# lia_dfu_fix.net
KiCad netlist of a schematic drawn in EAGLE
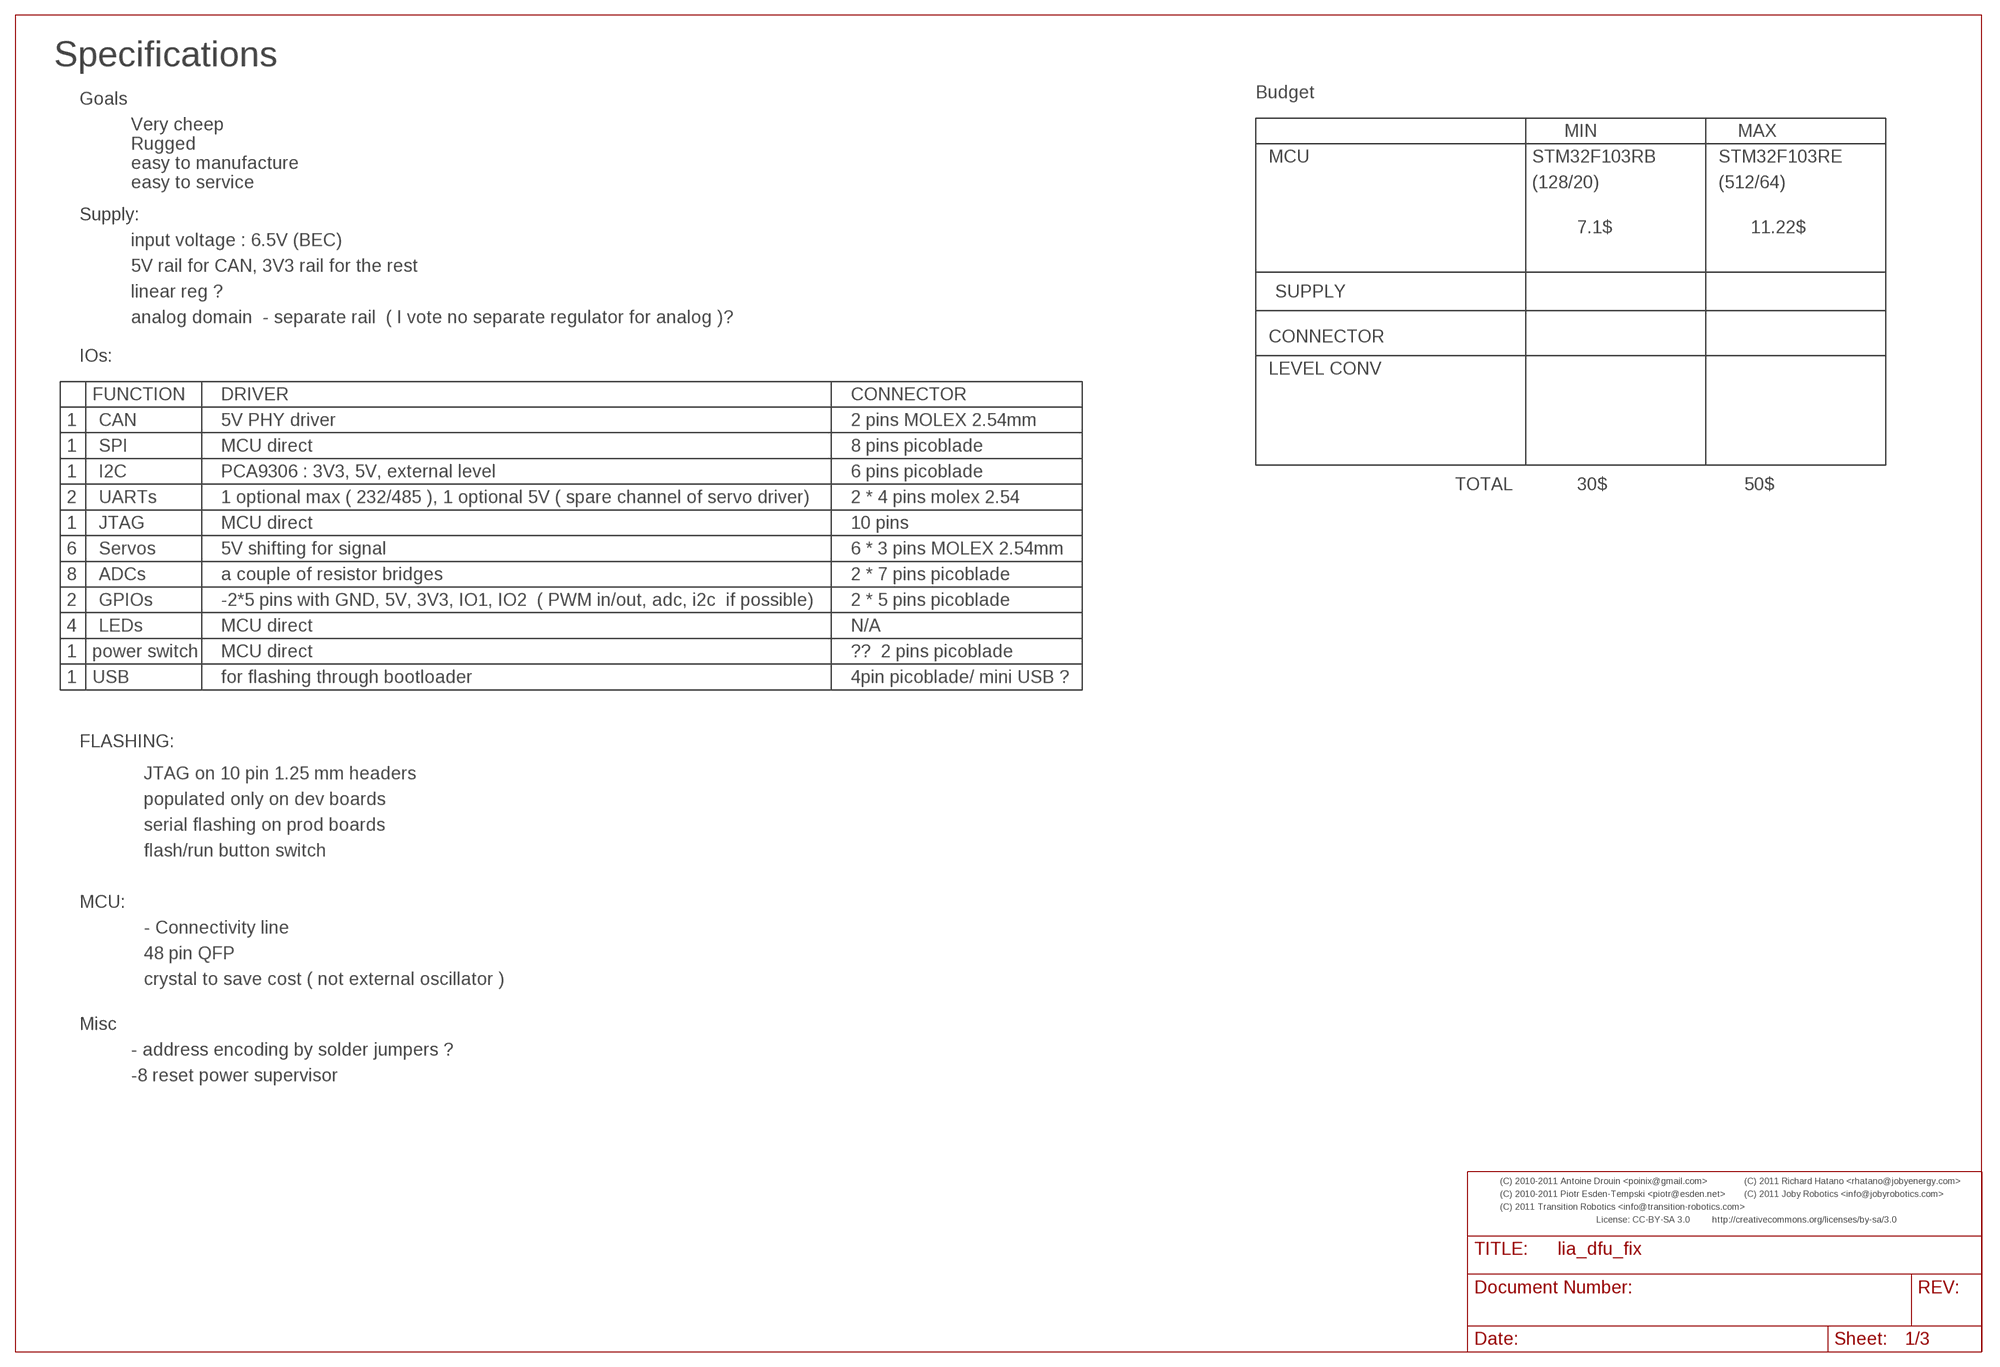
[diagram p0: schematic, sheet 1]
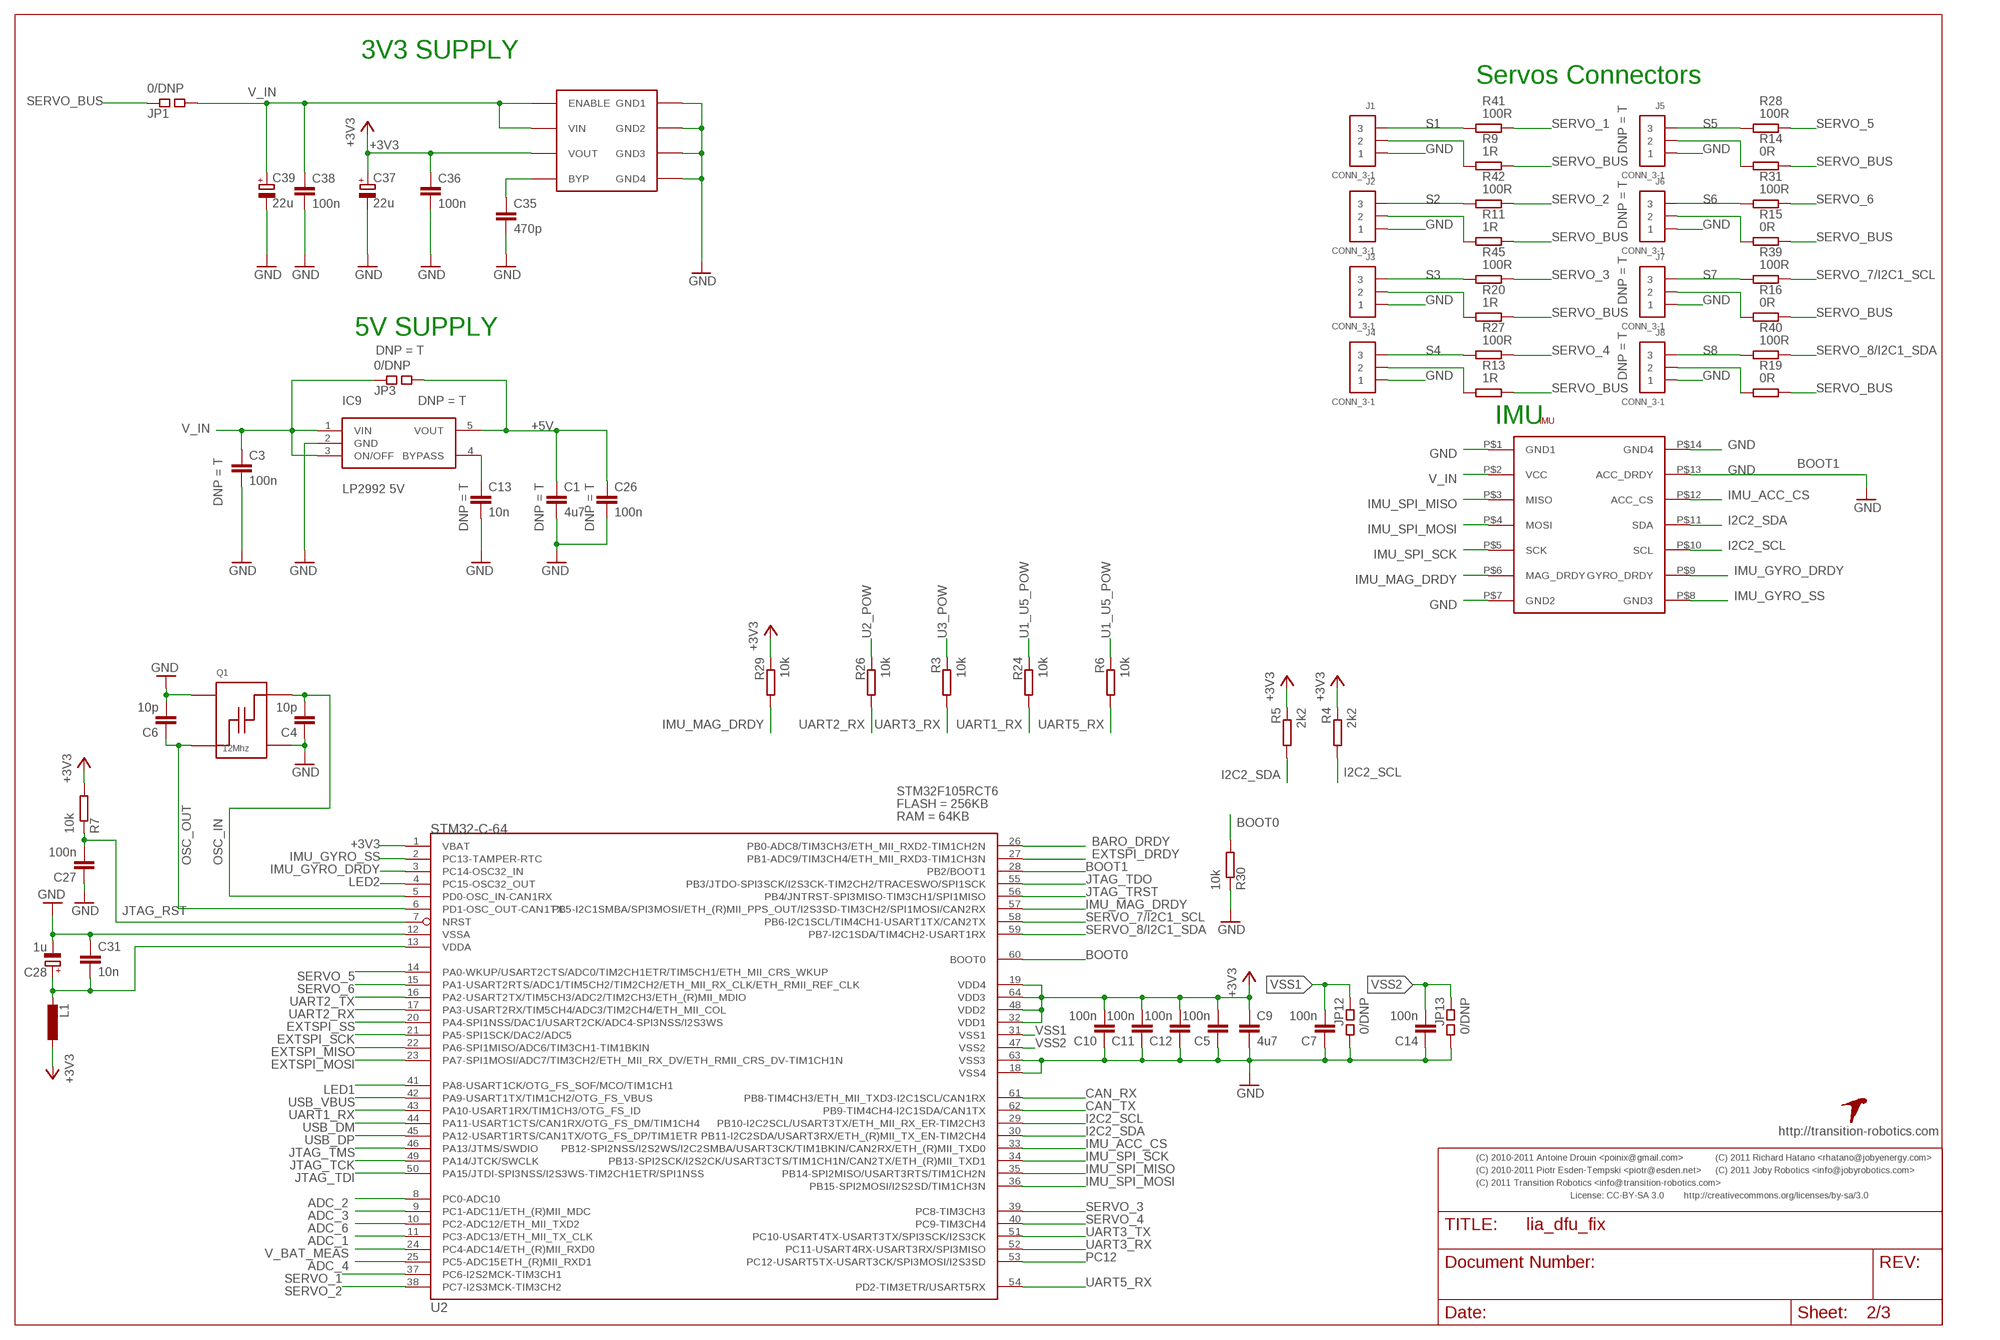
[diagram p1: schematic, sheet 2]
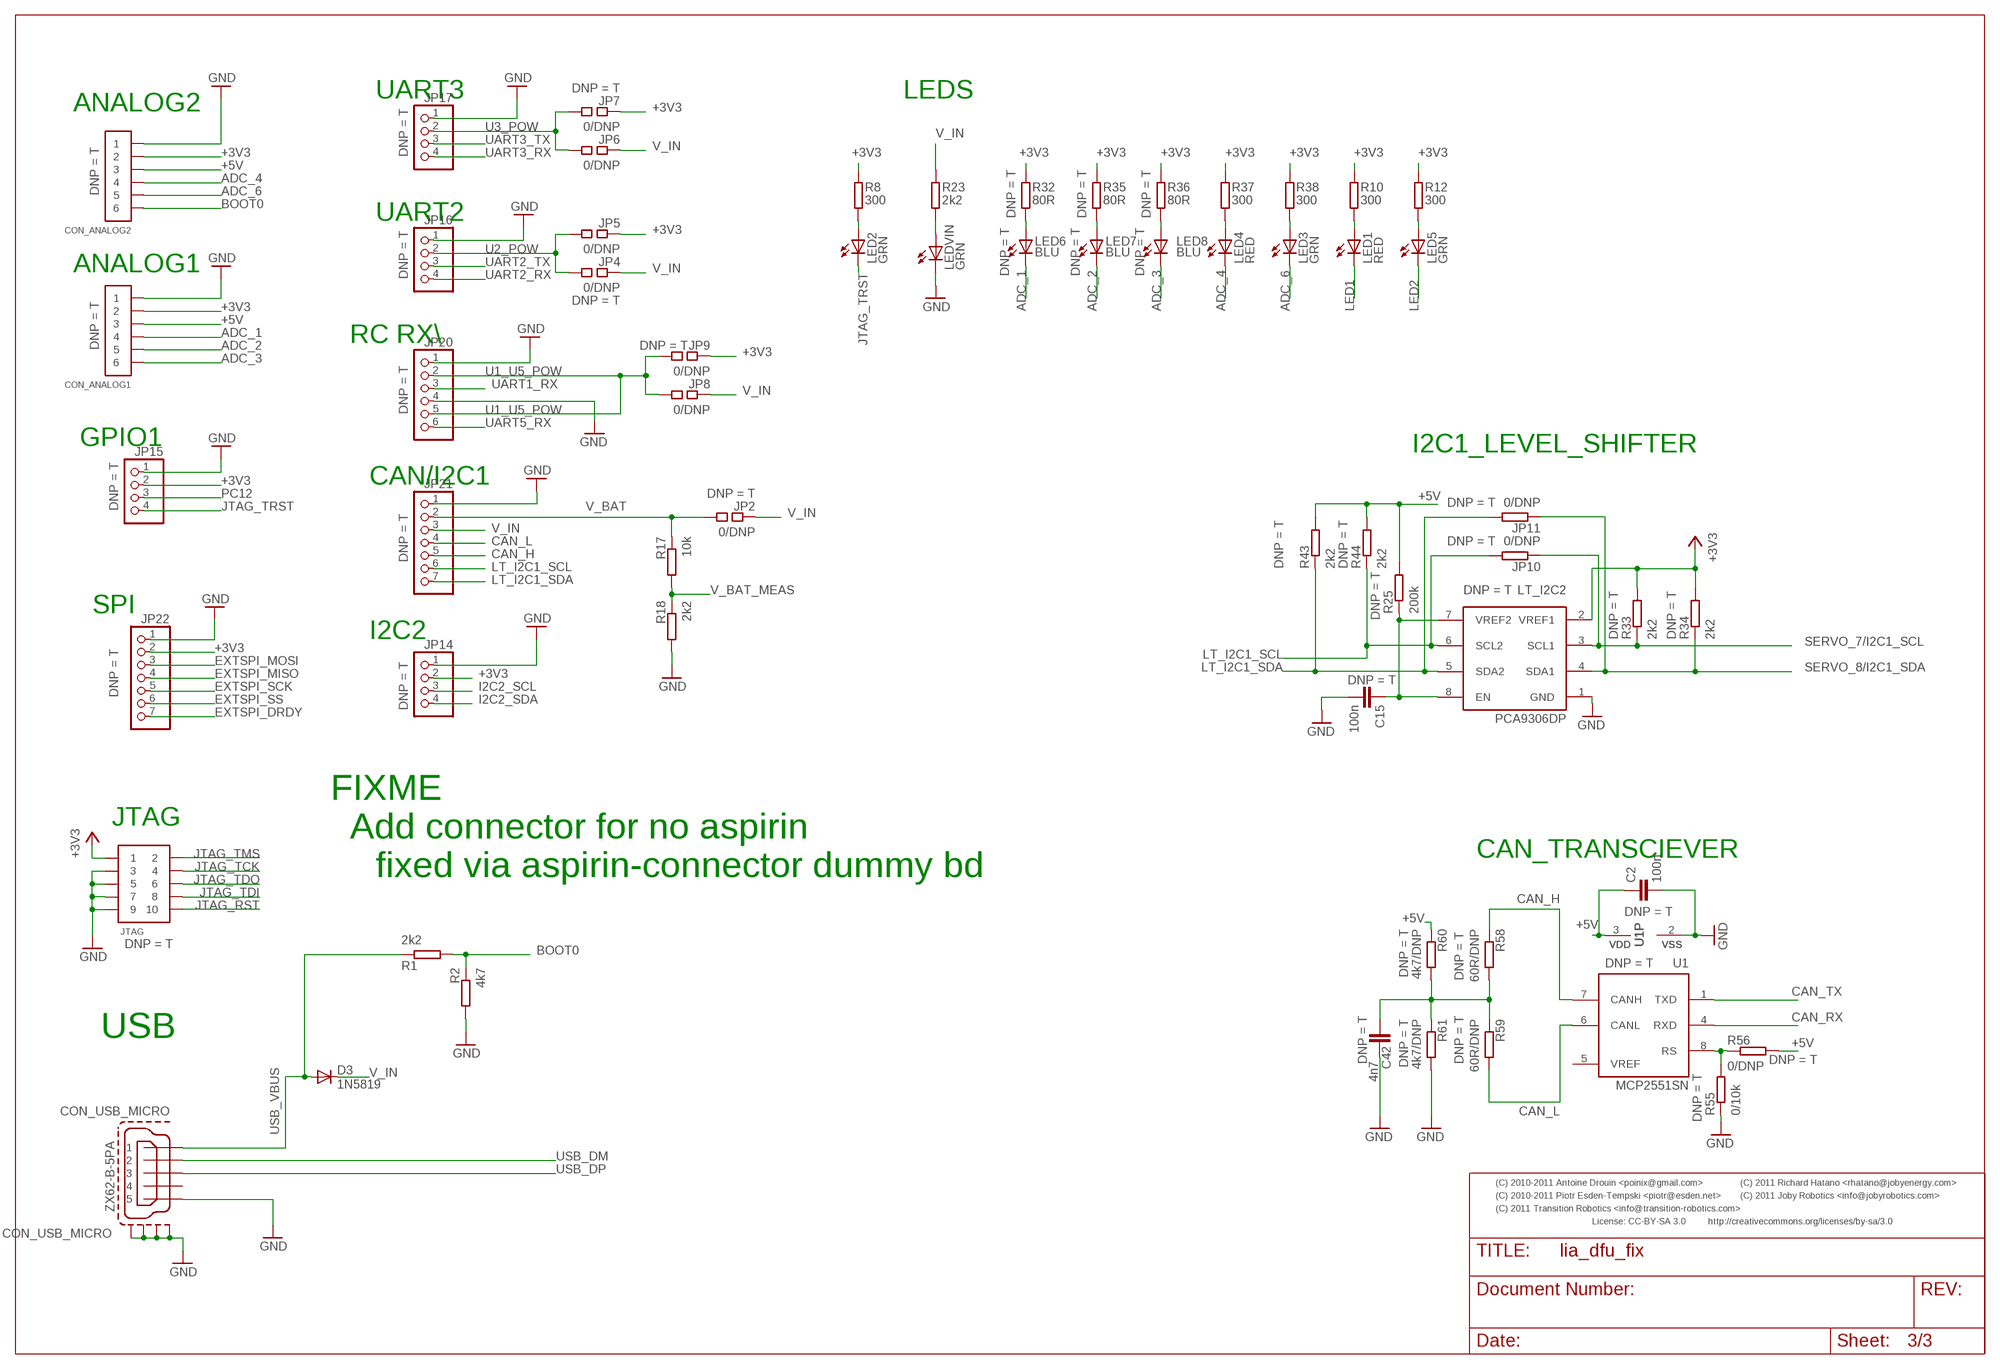
[diagram p2: schematic, sheet 3]

(export (version "E")
  (design (tool "Eeschema 10.0.6"))
  (components
    (comp (ref "C2")
      (value "100n")
      (footprint "eagle-import:0402-CAP")
      (fields (field (name "DNP") "T") (field (name "PARTNO") "cap-cer-0402-100n"))
      (libsource (lib "eagle-import") (part "CAPACITOR-0402"))
    )
    (comp (ref "C15")
      (value "100n")
      (footprint "eagle-import:0402-CAP")
      (fields (field (name "DNP") "T") (field (name "PARTNO") "cap-cer-0402-100n"))
      (libsource (lib "eagle-import") (part "CAPACITOR-0402"))
    )
    (comp (ref "C42")
      (value "4n7")
      (footprint "eagle-import:0603-CAP")
      (fields (field (name "DNP") "T") (field (name "PARTNO") "cap-cer-0603-4n7"))
      (libsource (lib "eagle-import") (part "CAPACITOR-0603"))
    )
    (comp (ref "CON_ANALOG1")
      (value "CONN_6-1-53398")
      (footprint "eagle-import:PB-53398-06")
      (fields (field (name "DNP") "T") (field (name "PARTNO") "conn-picoblade-smd-0.05in-6-vert"))
      (libsource (lib "eagle-import") (part "CONN_6-1-53398"))
    )
    (comp (ref "CON_ANALOG2")
      (value "CONN_6-1-53398")
      (footprint "eagle-import:PB-53398-06")
      (fields (field (name "DNP") "T") (field (name "PARTNO") "conn-picoblade-smd-0.05in-6-vert"))
      (libsource (lib "eagle-import") (part "CONN_6-1-53398"))
    )
    (comp (ref "CON_USB_MICRO")
      (value "ZX62-B-5PA")
      (footprint "eagle-import:ZX62-B-5PA")
      (fields (field (name "PARTNO") "conn-smd-usb-micro-b"))
      (libsource (lib "eagle-import") (part "ZX62-B-5PA"))
    )
    (comp (ref "D3")
      (value "1N5819")
      (footprint "eagle-import:MICROMELF-R")
      (fields (field (name "PARTNO") "diode-schottky-1608"))
      (libsource (lib "eagle-import") (part "DIODE-MICROMELF-R"))
    )
    (comp (ref "JP2")
      (value "0/DNP")
      (footprint "eagle-import:0402-SQJMP")
      (fields (field (name "DNP") "T") (field (name "PARTNO") "res-0402-0"))
      (libsource (lib "eagle-import") (part "SQ_JMP-0402"))
    )
    (comp (ref "JP4")
      (value "0/DNP")
      (footprint "eagle-import:0402-SQJMP")
      (fields (field (name "DNP") "T") (field (name "PARTNO") "res-0402-0"))
      (libsource (lib "eagle-import") (part "SQ_JMP-0402"))
    )
    (comp (ref "JP5")
      (value "0/DNP")
      (footprint "eagle-import:0402-SQJMP")
      (fields (field (name "PARTNO") "res-0402-0"))
      (libsource (lib "eagle-import") (part "SQ_JMP-0402"))
    )
    (comp (ref "JP6")
      (value "0/DNP")
      (footprint "eagle-import:0402-SQJMP")
      (fields (field (name "PARTNO") "res-0402-0"))
      (libsource (lib "eagle-import") (part "SQ_JMP-0402"))
    )
    (comp (ref "JP7")
      (value "0/DNP")
      (footprint "eagle-import:0402-SQJMP")
      (fields (field (name "DNP") "T") (field (name "PARTNO") "res-0402-0"))
      (libsource (lib "eagle-import") (part "SQ_JMP-0402"))
    )
    (comp (ref "JP8")
      (value "0/DNP")
      (footprint "eagle-import:0402-SQJMP")
      (fields (field (name "PARTNO") "res-0402-0"))
      (libsource (lib "eagle-import") (part "SQ_JMP-0402"))
    )
    (comp (ref "JP9")
      (value "0/DNP")
      (footprint "eagle-import:0402-SQJMP")
      (fields (field (name "DNP") "T") (field (name "PARTNO") "res-0402-0"))
      (libsource (lib "eagle-import") (part "SQ_JMP-0402"))
    )
    (comp (ref "JP10")
      (value "0/DNP")
      (footprint "eagle-import:0603-RES")
      (fields (field (name "DNP") "T") (field (name "PARTNO") "res-0603-0"))
      (libsource (lib "eagle-import") (part "RESISTOR-0603"))
    )
    (comp (ref "JP11")
      (value "0/DNP")
      (footprint "eagle-import:0603-RES")
      (fields (field (name "DNP") "T") (field (name "PARTNO") "res-0603-0"))
      (libsource (lib "eagle-import") (part "RESISTOR-0603"))
    )
    (comp (ref "JP14")
      (value "PINHD-1X4")
      (footprint "eagle-import:1X04")
      (fields (field (name "DNP") "T") (field (name "PARTNO") "conn-th-0.1in-4-1"))
      (libsource (lib "eagle-import") (part "PINHD-1X4"))
    )
    (comp (ref "JP15")
      (value "PINHD-1X4")
      (footprint "eagle-import:1X04")
      (fields (field (name "DNP") "T") (field (name "PARTNO") "conn-th-0.1in-4-1"))
      (libsource (lib "eagle-import") (part "PINHD-1X4"))
    )
    (comp (ref "JP16")
      (value "PINHD-1X4")
      (footprint "eagle-import:1X04")
      (fields (field (name "DNP") "T") (field (name "PARTNO") "conn-th-0.1in-4-1"))
      (libsource (lib "eagle-import") (part "PINHD-1X4"))
    )
    (comp (ref "JP17")
      (value "PINHD-1X4")
      (footprint "eagle-import:1X04")
      (fields (field (name "DNP") "T") (field (name "PARTNO") "conn-th-0.1in-4-1"))
      (libsource (lib "eagle-import") (part "PINHD-1X4"))
    )
    (comp (ref "JP20")
      (value "PINHD-1X6")
      (footprint "eagle-import:1X06")
      (fields (field (name "DNP") "T") (field (name "PARTNO") "conn-th-0.1in-6-1"))
      (libsource (lib "eagle-import") (part "PINHD-1X6"))
    )
    (comp (ref "JP21")
      (value "PINHD-1X7")
      (footprint "eagle-import:1X07")
      (fields (field (name "DNP") "T") (field (name "PARTNO") "conn-th-0.1in-7-1"))
      (libsource (lib "eagle-import") (part "PINHD-1X7"))
    )
    (comp (ref "JP22")
      (value "PINHD-1X7")
      (footprint "eagle-import:1X07")
      (fields (field (name "DNP") "T") (field (name "PARTNO") "conn-th-0.1in-7-1"))
      (libsource (lib "eagle-import") (part "PINHD-1X7"))
    )
    (comp (ref "JTAG")
      (value "PIN_HDR_EDG_1.27MM_5-2")
      (footprint "eagle-import:FTSH-105-DV")
      (fields (field (name "DNP") "T") (field (name "PARTNO") "conn-smd-0.05in-5-2"))
      (libsource (lib "eagle-import") (part "CONN_5-2-FTSH-V"))
    )
    (comp (ref "LED1")
      (value "RED")
      (footprint "eagle-import:0402-LED")
      (fields (field (name "PARTNO") "led-0402-red"))
      (libsource (lib "eagle-import") (part "LED-0402"))
    )
    (comp (ref "LED2")
      (value "GRN")
      (footprint "eagle-import:0402-LED")
      (fields (field (name "PARTNO") "led-0402-green"))
      (libsource (lib "eagle-import") (part "LED-0402"))
    )
    (comp (ref "LED3")
      (value "GRN")
      (footprint "eagle-import:0402-LED")
      (fields (field (name "PARTNO") "led-0402-green"))
      (libsource (lib "eagle-import") (part "LED-0402"))
    )
    (comp (ref "LED4")
      (value "RED")
      (footprint "eagle-import:0402-LED")
      (fields (field (name "PARTNO") "led-0402-red"))
      (libsource (lib "eagle-import") (part "LED-0402"))
    )
    (comp (ref "LED5")
      (value "GRN")
      (footprint "eagle-import:0402-LED")
      (fields (field (name "PARTNO") "led-0402-green"))
      (libsource (lib "eagle-import") (part "LED-0402"))
    )
    (comp (ref "LED6")
      (value "BLU")
      (footprint "eagle-import:0402-LED")
      (fields (field (name "DNP") "T") (field (name "PARTNO") "led-0402-blue"))
      (libsource (lib "eagle-import") (part "LED-0402"))
    )
    (comp (ref "LED7")
      (value "BLU")
      (footprint "eagle-import:0402-LED")
      (fields (field (name "DNP") "T") (field (name "PARTNO") "led-0402-blue"))
      (libsource (lib "eagle-import") (part "LED-0402"))
    )
    (comp (ref "LED8")
      (value "BLU")
      (footprint "eagle-import:0402-LED")
      (fields (field (name "DNP") "T") (field (name "PARTNO") "led-0402-blue"))
      (libsource (lib "eagle-import") (part "LED-0402"))
    )
    (comp (ref "LEDVIN")
      (value "GRN")
      (footprint "eagle-import:0402-LED")
      (fields (field (name "PARTNO") "led-0402-green"))
      (libsource (lib "eagle-import") (part "LED-0402"))
    )
    (comp (ref "LT_I2C2")
      (value "PCA9306DP")
      (footprint "eagle-import:TSSOP_B3")
      (fields (field (name "DNP") "T") (field (name "PARTNO") "ic-tssop8-level-trans"))
      (libsource (lib "eagle-import") (part "PCA9306DP"))
    )
    (comp (ref "R1")
      (value "2k2")
      (footprint "eagle-import:0402-RES")
      (fields (field (name "PARTNO") "res-0402-2k2"))
      (libsource (lib "eagle-import") (part "RESISTOR-0402"))
    )
    (comp (ref "R2")
      (value "4k7")
      (footprint "eagle-import:0402-RES")
      (fields (field (name "PARTNO") "res-0402-2k2"))
      (libsource (lib "eagle-import") (part "RESISTOR-0402"))
    )
    (comp (ref "R8")
      (value "300")
      (footprint "eagle-import:0402-RES")
      (fields (field (name "PARTNO") "res-0402-300"))
      (libsource (lib "eagle-import") (part "RESISTOR-0402"))
    )
    (comp (ref "R10")
      (value "300")
      (footprint "eagle-import:0402-RES")
      (fields (field (name "PARTNO") "res-0402-300"))
      (libsource (lib "eagle-import") (part "RESISTOR-0402"))
    )
    (comp (ref "R12")
      (value "300")
      (footprint "eagle-import:0402-RES")
      (fields (field (name "PARTNO") "res-0402-300"))
      (libsource (lib "eagle-import") (part "RESISTOR-0402"))
    )
    (comp (ref "R17")
      (value "10k")
      (footprint "eagle-import:0402-RES")
      (fields (field (name "PARTNO") "res-0402-10k"))
      (libsource (lib "eagle-import") (part "RESISTOR-0402"))
    )
    (comp (ref "R18")
      (value "2k2")
      (footprint "eagle-import:0402-RES")
      (fields (field (name "PARTNO") "res-0402-2k2"))
      (libsource (lib "eagle-import") (part "RESISTOR-0402"))
    )
    (comp (ref "R23")
      (value "2k2")
      (footprint "eagle-import:0402-RES")
      (fields (field (name "PARTNO") "res-0402-2k2"))
      (libsource (lib "eagle-import") (part "RESISTOR-0402"))
    )
    (comp (ref "R25")
      (value "200k")
      (footprint "eagle-import:0402-RES")
      (fields (field (name "DNP") "T") (field (name "PARTNO") "res-0402-200k"))
      (libsource (lib "eagle-import") (part "RESISTOR-0402"))
    )
    (comp (ref "R32")
      (value "80R")
      (footprint "eagle-import:0402-RES")
      (fields (field (name "DNP") "T") (field (name "PARTNO") "res-0402-80"))
      (libsource (lib "eagle-import") (part "RESISTOR-0402"))
    )
    (comp (ref "R33")
      (value "2k2")
      (footprint "eagle-import:0402-RES")
      (fields (field (name "DNP") "T") (field (name "PARTNO") "res-0402-2k2"))
      (libsource (lib "eagle-import") (part "RESISTOR-0402"))
    )
    (comp (ref "R34")
      (value "2k2")
      (footprint "eagle-import:0402-RES")
      (fields (field (name "DNP") "T") (field (name "PARTNO") "res-0402-2k2"))
      (libsource (lib "eagle-import") (part "RESISTOR-0402"))
    )
    (comp (ref "R35")
      (value "80R")
      (footprint "eagle-import:0402-RES")
      (fields (field (name "DNP") "T") (field (name "PARTNO") "res-0402-80"))
      (libsource (lib "eagle-import") (part "RESISTOR-0402"))
    )
    (comp (ref "R36")
      (value "80R")
      (footprint "eagle-import:0402-RES")
      (fields (field (name "DNP") "T") (field (name "PARTNO") "res-0402-80"))
      (libsource (lib "eagle-import") (part "RESISTOR-0402"))
    )
    (comp (ref "R37")
      (value "300")
      (footprint "eagle-import:0402-RES")
      (fields (field (name "PARTNO") "res-0402-300"))
      (libsource (lib "eagle-import") (part "RESISTOR-0402"))
    )
    (comp (ref "R38")
      (value "300")
      (footprint "eagle-import:0402-RES")
      (fields (field (name "PARTNO") "res-0402-300"))
      (libsource (lib "eagle-import") (part "RESISTOR-0402"))
    )
    (comp (ref "R43")
      (value "2k2")
      (footprint "eagle-import:0402-RES")
      (fields (field (name "DNP") "T") (field (name "PARTNO") "res-0402-1k5"))
      (libsource (lib "eagle-import") (part "RESISTOR-0402"))
    )
    (comp (ref "R44")
      (value "2k2")
      (footprint "eagle-import:0402-RES")
      (fields (field (name "DNP") "T") (field (name "PARTNO") "res-0402-1k5"))
      (libsource (lib "eagle-import") (part "RESISTOR-0402"))
    )
    (comp (ref "R55")
      (value "0/10k")
      (footprint "eagle-import:0402-RES")
      (fields (field (name "DNP") "T") (field (name "PARTNO") "res-0402-10k"))
      (libsource (lib "eagle-import") (part "RESISTOR-0402"))
    )
    (comp (ref "R56")
      (value "0/DNP")
      (footprint "eagle-import:0402-RES")
      (fields (field (name "DNP") "T") (field (name "PARTNO") "res-0402-0"))
      (libsource (lib "eagle-import") (part "RESISTOR-0402"))
    )
    (comp (ref "R58")
      (value "60R/DNP")
      (footprint "eagle-import:0402-RES")
      (fields (field (name "DNP") "T") (field (name "PARTNO") "res-0402-60.4"))
      (libsource (lib "eagle-import") (part "RESISTOR-0402"))
    )
    (comp (ref "R59")
      (value "60R/DNP")
      (footprint "eagle-import:0402-RES")
      (fields (field (name "DNP") "T") (field (name "PARTNO") "res-0402-60.4"))
      (libsource (lib "eagle-import") (part "RESISTOR-0402"))
    )
    (comp (ref "R60")
      (value "4k7/DNP")
      (footprint "eagle-import:0402-RES")
      (fields (field (name "DNP") "T") (field (name "PARTNO") "res-0402-4k7"))
      (libsource (lib "eagle-import") (part "RESISTOR-0402"))
    )
    (comp (ref "R61")
      (value "4k7/DNP")
      (footprint "eagle-import:0402-RES")
      (fields (field (name "DNP") "T") (field (name "PARTNO") "res-0402-4k7"))
      (libsource (lib "eagle-import") (part "RESISTOR-0402"))
    )
    (comp (ref "U1")
      (value "MCP2551SN")
      (footprint "eagle-import:SO-08")
      (fields (field (name "DNP") "T") (field (name "PARTNO") "ic-so8-can"))
      (libsource (lib "eagle-import") (part "MCP2551SN"))
    )
    (comp (ref "C1")
      (value "4u7")
      (footprint "eagle-import:0805-CAP")
      (fields (field (name "DNP") "T") (field (name "PARTNO") "cap-cer-0805-4u7"))
      (libsource (lib "eagle-import") (part "CAPACITOR-0805"))
    )
    (comp (ref "C3")
      (value "100n")
      (footprint "eagle-import:0603-CAP")
      (fields (field (name "DNP") "T") (field (name "PARTNO") "cap-cer-0603-100n"))
      (libsource (lib "eagle-import") (part "CAPACITOR-0603"))
    )
    (comp (ref "C4")
      (value "10p")
      (footprint "eagle-import:0402-CAP")
      (fields (field (name "PARTNO") "cap-cer-0402-10p"))
      (libsource (lib "eagle-import") (part "CAPACITOR-0402"))
    )
    (comp (ref "C5")
      (value "100n")
      (footprint "eagle-import:0402-CAP")
      (fields (field (name "PARTNO") "cap-cer-0402-100n"))
      (libsource (lib "eagle-import") (part "CAPACITOR-0402"))
    )
    (comp (ref "C6")
      (value "10p")
      (footprint "eagle-import:0402-CAP")
      (fields (field (name "PARTNO") "cap-cer-0402-10p"))
      (libsource (lib "eagle-import") (part "CAPACITOR-0402"))
    )
    (comp (ref "C7")
      (value "100n")
      (footprint "eagle-import:0402-CAP")
      (fields (field (name "PARTNO") "cap-cer-0402-100n"))
      (libsource (lib "eagle-import") (part "CAPACITOR-0402"))
    )
    (comp (ref "C9")
      (value "4u7")
      (footprint "eagle-import:0805-CAP")
      (fields (field (name "PARTNO") "cap-cer-0805-4u7"))
      (libsource (lib "eagle-import") (part "CAPACITOR-0805"))
    )
    (comp (ref "C10")
      (value "100n")
      (footprint "eagle-import:0402-CAP")
      (fields (field (name "PARTNO") "cap-cer-0402-100n"))
      (libsource (lib "eagle-import") (part "CAPACITOR-0402"))
    )
    (comp (ref "C11")
      (value "100n")
      (footprint "eagle-import:0402-CAP")
      (fields (field (name "PARTNO") "cap-cer-0402-100n"))
      (libsource (lib "eagle-import") (part "CAPACITOR-0402"))
    )
    (comp (ref "C12")
      (value "100n")
      (footprint "eagle-import:0402-CAP")
      (fields (field (name "PARTNO") "cap-cer-0402-100n"))
      (libsource (lib "eagle-import") (part "CAPACITOR-0402"))
    )
    (comp (ref "C13")
      (value "10n")
      (footprint "eagle-import:0402-CAP")
      (fields (field (name "DNP") "T") (field (name "PARTNO") "cap-cer-0402-10n"))
      (libsource (lib "eagle-import") (part "CAPACITOR-0402"))
    )
    (comp (ref "C14")
      (value "100n")
      (footprint "eagle-import:0402-CAP")
      (fields (field (name "PARTNO") "cap-cer-0402-100n"))
      (libsource (lib "eagle-import") (part "CAPACITOR-0402"))
    )
    (comp (ref "C26")
      (value "100n")
      (footprint "eagle-import:0603-CAP")
      (fields (field (name "DNP") "T") (field (name "PARTNO") "cap-cer-0603-100n"))
      (libsource (lib "eagle-import") (part "CAPACITOR-0603"))
    )
    (comp (ref "C27")
      (value "100n")
      (footprint "eagle-import:0402-CAP")
      (fields (field (name "PARTNO") "cap-cer-0402-100n"))
      (libsource (lib "eagle-import") (part "CAPACITOR-0402"))
    )
    (comp (ref "C28")
      (value "1u")
      (footprint "eagle-import:0603-POL-CAP")
      (fields (field (name "PARTNO") "cap-tan-0603-1u"))
      (libsource (lib "eagle-import") (part "CAPACITOR-POL-0603"))
    )
    (comp (ref "C31")
      (value "10n")
      (footprint "eagle-import:0402-CAP")
      (fields (field (name "PARTNO") "cap-cer-0402-10n"))
      (libsource (lib "eagle-import") (part "CAPACITOR-0402"))
    )
    (comp (ref "C35")
      (value "470p")
      (footprint "eagle-import:0402-CAP")
      (fields (field (name "PARTNO") "cap-cer-0402-470p"))
      (libsource (lib "eagle-import") (part "CAPACITOR-0402"))
    )
    (comp (ref "C36")
      (value "100n")
      (footprint "eagle-import:0603-CAP")
      (fields (field (name "PARTNO") "cap-cer-0603-100n"))
      (libsource (lib "eagle-import") (part "CAPACITOR-0603"))
    )
    (comp (ref "C37")
      (value "22u")
      (footprint "eagle-import:3528_B")
      (fields (field (name "PARTNO") "cap-tan-B-22u-16v"))
      (libsource (lib "eagle-import") (part "CAPACITOR-POLB"))
    )
    (comp (ref "C38")
      (value "100n")
      (footprint "eagle-import:0402-CAP")
      (fields (field (name "PARTNO") "cap-cer-0402-100n"))
      (libsource (lib "eagle-import") (part "CAPACITOR-0402"))
    )
    (comp (ref "C39")
      (value "22u")
      (footprint "eagle-import:3528_B")
      (fields (field (name "PARTNO") "cap-tan-B-22u-16v"))
      (libsource (lib "eagle-import") (part "CAPACITOR-POLB"))
    )
    (comp (ref "IC9")
      (value "LP2992 5V")
      (footprint "eagle-import:SOT23-5")
      (fields (field (name "DNP") "T") (field (name "PARTNO") "vreg-sot-23-5-5v"))
      (libsource (lib "eagle-import") (part "LP2992"))
    )
    (comp (ref "IMU")
      (value "ASPIRIN")
      (footprint "eagle-import:ASPIRIN_1")
      (fields (field (name "PARTNO") "pcb-ass-aspirin"))
      (libsource (lib "eagle-import") (part "ASPIRIN"))
    )
    (comp (ref "J1")
      (value "CONN_3-1")
      (footprint "eagle-import:SIP1X3_100")
      (fields (field (name "PARTNO") "conn-th-0.1in-3-2-ra"))
      (libsource (lib "eagle-import") (part "CONN_3-1"))
    )
    (comp (ref "J2")
      (value "CONN_3-1")
      (footprint "eagle-import:SIP1X3_100")
      (fields (field (name "PARTNO") "conn-th-0.1in-3-2-ra"))
      (libsource (lib "eagle-import") (part "CONN_3-1"))
    )
    (comp (ref "J3")
      (value "CONN_3-1")
      (footprint "eagle-import:SIP1X3_100")
      (fields (field (name "PARTNO") "conn-th-0.1in-3-2-ra"))
      (libsource (lib "eagle-import") (part "CONN_3-1"))
    )
    (comp (ref "J4")
      (value "CONN_3-1")
      (footprint "eagle-import:SIP1X3_100")
      (fields (field (name "PARTNO") "conn-th-0.1in-3-2-ra"))
      (libsource (lib "eagle-import") (part "CONN_3-1"))
    )
    (comp (ref "J5")
      (value "CONN_3-1")
      (footprint "eagle-import:SIP1X3_100")
      (fields (field (name "DNP") "T") (field (name "PARTNO") "conn-th-0.1in-3-2-ra"))
      (libsource (lib "eagle-import") (part "CONN_3-1"))
    )
    (comp (ref "J6")
      (value "CONN_3-1")
      (footprint "eagle-import:SIP1X3_100")
      (fields (field (name "DNP") "T") (field (name "PARTNO") "conn-th-0.1in-3-2-ra"))
      (libsource (lib "eagle-import") (part "CONN_3-1"))
    )
    (comp (ref "J7")
      (value "CONN_3-1")
      (footprint "eagle-import:SIP1X3_100")
      (fields (field (name "DNP") "T") (field (name "PARTNO") "conn-th-0.1in-3-2-ra"))
      (libsource (lib "eagle-import") (part "CONN_3-1"))
    )
    (comp (ref "J8")
      (value "CONN_3-1")
      (footprint "eagle-import:SIP1X3_100")
      (fields (field (name "DNP") "T") (field (name "PARTNO") "conn-th-0.1in-3-2-ra"))
      (libsource (lib "eagle-import") (part "CONN_3-1"))
    )
    (comp (ref "JP1")
      (value "0/DNP")
      (footprint "eagle-import:0402-SQJMP")
      (fields (field (name "PARTNO") "res-0402-0"))
      (libsource (lib "eagle-import") (part "SQ_JMP-0402"))
    )
    (comp (ref "JP3")
      (value "0/DNP")
      (footprint "eagle-import:0402-SQJMP")
      (fields (field (name "DNP") "T") (field (name "PARTNO") "res-0402-0"))
      (libsource (lib "eagle-import") (part "SQ_JMP-0402"))
    )
    (comp (ref "JP12")
      (value "0/DNP")
      (footprint "eagle-import:0402-SQJMP")
      (fields (field (name "PARTNO") "res-0402-0"))
      (libsource (lib "eagle-import") (part "SQ_JMP-0402"))
    )
    (comp (ref "JP13")
      (value "0/DNP")
      (footprint "eagle-import:0402-SQJMP")
      (fields (field (name "PARTNO") "res-0402-0"))
      (libsource (lib "eagle-import") (part "SQ_JMP-0402"))
    )
    (comp (ref "L1")
      (value "INDUCTOR-0603")
      (footprint "eagle-import:0603-IND")
      (fields (field (name "PARTNO") "ferrite-0603-600ohm"))
      (libsource (lib "eagle-import") (part "INDUCTOR-0603"))
    )
    (comp (ref "Q1")
      (value "12Mhz")
      (footprint "eagle-import:ABM8")
      (fields (field (name "PARTNO") "xtal-abm8-12mhz"))
      (libsource (lib "eagle-import") (part "ABM8"))
    )
    (comp (ref "R3")
      (value "10k")
      (footprint "eagle-import:0402-RES")
      (fields (field (name "PARTNO") "res-0402-10k"))
      (libsource (lib "eagle-import") (part "RESISTOR-0402"))
    )
    (comp (ref "R4")
      (value "2k2")
      (footprint "eagle-import:0402-RES")
      (fields (field (name "PARTNO") "res-0402-2k2"))
      (libsource (lib "eagle-import") (part "RESISTOR-0402"))
    )
    (comp (ref "R5")
      (value "2k2")
      (footprint "eagle-import:0402-RES")
      (fields (field (name "PARTNO") "res-0402-2k2"))
      (libsource (lib "eagle-import") (part "RESISTOR-0402"))
    )
    (comp (ref "R6")
      (value "10k")
      (footprint "eagle-import:0402-RES")
      (fields (field (name "PARTNO") "res-0402-10k"))
      (libsource (lib "eagle-import") (part "RESISTOR-0402"))
    )
    (comp (ref "R7")
      (value "10k")
      (footprint "eagle-import:0402-RES")
      (fields (field (name "PARTNO") "res-0402-10k"))
      (libsource (lib "eagle-import") (part "RESISTOR-0402"))
    )
    (comp (ref "R9")
      (value "1R")
      (footprint "eagle-import:1206-RES")
      (fields (field (name "PARTNO") "res-1206-1"))
      (libsource (lib "eagle-import") (part "RESISTOR-1206"))
    )
    (comp (ref "R11")
      (value "1R")
      (footprint "eagle-import:1206-RES")
      (fields (field (name "PARTNO") "res-1206-1"))
      (libsource (lib "eagle-import") (part "RESISTOR-1206"))
    )
    (comp (ref "R13")
      (value "1R")
      (footprint "eagle-import:1206-RES")
      (fields (field (name "PARTNO") "res-1206-1"))
      (libsource (lib "eagle-import") (part "RESISTOR-1206"))
    )
    (comp (ref "R14")
      (value "0R")
      (footprint "eagle-import:1206-RES")
      (fields (field (name "PARTNO") "res-1206-0"))
      (libsource (lib "eagle-import") (part "RESISTOR-1206"))
    )
    (comp (ref "R15")
      (value "0R")
      (footprint "eagle-import:1206-RES")
      (fields (field (name "PARTNO") "res-1206-0"))
      (libsource (lib "eagle-import") (part "RESISTOR-1206"))
    )
    (comp (ref "R16")
      (value "0R")
      (footprint "eagle-import:1206-RES")
      (fields (field (name "PARTNO") "res-1206-0"))
      (libsource (lib "eagle-import") (part "RESISTOR-1206"))
    )
    (comp (ref "R19")
      (value "0R")
      (footprint "eagle-import:1206-RES")
      (fields (field (name "PARTNO") "res-1206-0"))
      (libsource (lib "eagle-import") (part "RESISTOR-1206"))
    )
    (comp (ref "R20")
      (value "1R")
      (footprint "eagle-import:1206-RES")
      (fields (field (name "PARTNO") "res-1206-1"))
      (libsource (lib "eagle-import") (part "RESISTOR-1206"))
    )
    (comp (ref "R24")
      (value "10k")
      (footprint "eagle-import:0402-RES")
      (fields (field (name "PARTNO") "res-0402-10k"))
      (libsource (lib "eagle-import") (part "RESISTOR-0402"))
    )
    (comp (ref "R26")
      (value "10k")
      (footprint "eagle-import:0402-RES")
      (fields (field (name "PARTNO") "res-0402-10k"))
      (libsource (lib "eagle-import") (part "RESISTOR-0402"))
    )
    (comp (ref "R27")
      (value "100R")
      (footprint "eagle-import:0402-RES")
      (fields (field (name "PARTNO") "res-0402-100"))
      (libsource (lib "eagle-import") (part "RESISTOR-0402"))
    )
    (comp (ref "R28")
      (value "100R")
      (footprint "eagle-import:0402-RES")
      (fields (field (name "PARTNO") "res-0402-100"))
      (libsource (lib "eagle-import") (part "RESISTOR-0402"))
    )
    (comp (ref "R29")
      (value "10k")
      (footprint "eagle-import:0402-RES")
      (fields (field (name "PARTNO") "res-0402-10k"))
      (libsource (lib "eagle-import") (part "RESISTOR-0402"))
    )
    (comp (ref "R30")
      (value "10k")
      (footprint "eagle-import:0402-RES")
      (fields (field (name "PARTNO") "res-0402-10k"))
      (libsource (lib "eagle-import") (part "RESISTOR-0402"))
    )
    (comp (ref "R31")
      (value "100R")
      (footprint "eagle-import:0402-RES")
      (fields (field (name "PARTNO") "res-0402-100"))
      (libsource (lib "eagle-import") (part "RESISTOR-0402"))
    )
    (comp (ref "R39")
      (value "100R")
      (footprint "eagle-import:0402-RES")
      (fields (field (name "PARTNO") "res-0402-100"))
      (libsource (lib "eagle-import") (part "RESISTOR-0402"))
    )
    (comp (ref "R40")
      (value "100R")
      (footprint "eagle-import:0402-RES")
      (fields (field (name "PARTNO") "res-0402-100"))
      (libsource (lib "eagle-import") (part "RESISTOR-0402"))
    )
    (comp (ref "R41")
      (value "100R")
      (footprint "eagle-import:0402-RES")
      (fields (field (name "PARTNO") "res-0402-100"))
      (libsource (lib "eagle-import") (part "RESISTOR-0402"))
    )
    (comp (ref "R42")
      (value "100R")
      (footprint "eagle-import:0402-RES")
      (fields (field (name "PARTNO") "res-0402-100"))
      (libsource (lib "eagle-import") (part "RESISTOR-0402"))
    )
    (comp (ref "R45")
      (value "100R")
      (footprint "eagle-import:0402-RES")
      (fields (field (name "PARTNO") "res-0402-100"))
      (libsource (lib "eagle-import") (part "RESISTOR-0402"))
    )
    (comp (ref "U$1")
      (value "TR-LOGO")
      (footprint "eagle-import:TR-LOGO")
      (libsource (lib "eagle-import") (part "TR-LOGO"))
    )
    (comp (ref "U2")
      (value "STM32-C-64")
      (footprint "eagle-import:LQFP64")
      (fields
        (field (name "FLASH") "256KB")
        (field (name "PARTNO") "mcu-lqfp-64-stm32")
        (field (name "PART_NR") "STM32F105RCT6")
        (field (name "RAM") "64KB")
      )
      (libsource (lib "eagle-import") (part "STM32-C-64"))
    )
    (comp (ref "VREG1")
      (value "MIC5209")
      (footprint "eagle-import:SOIC8")
      (fields (field (name "PARTNO") "vreg-so8-3v3"))
      (libsource (lib "eagle-import") (part "MIC5209"))
    )
  )
  (nets
    (net (code "1") (name "+3V3") (class "Default")
      (node (ref "C10") (pin "P$2") (pinfunction "2_P$2") (pintype "passive"))
      (node (ref "C11") (pin "P$2") (pinfunction "2_P$2") (pintype "passive"))
      (node (ref "C12") (pin "P$2") (pinfunction "2_P$2") (pintype "passive"))
      (node (ref "C36") (pin "P$1") (pinfunction "1_P$1") (pintype "passive"))
      (node (ref "C37") (pin "+") (pinfunction "+_+") (pintype "passive"))
      (node (ref "C5") (pin "P$2") (pinfunction "2_P$2") (pintype "passive"))
      (node (ref "C9") (pin "P$1") (pinfunction "1_P$1") (pintype "passive"))
      (node (ref "CON_ANALOG1") (pin "2") (pinfunction "2_2") (pintype "bidirectional"))
      (node (ref "CON_ANALOG2") (pin "2") (pinfunction "2_2") (pintype "bidirectional"))
      (node (ref "JP14") (pin "2") (pinfunction "2_2") (pintype "passive"))
      (node (ref "JP15") (pin "2") (pinfunction "2_2") (pintype "passive"))
      (node (ref "JP22") (pin "2") (pinfunction "2_2") (pintype "passive"))
      (node (ref "JP5") (pin "P$1") (pinfunction "1_P$1") (pintype "passive"))
      (node (ref "JP7") (pin "P$1") (pinfunction "1_P$1") (pintype "passive"))
      (node (ref "JP9") (pin "P$1") (pinfunction "1_P$1") (pintype "passive"))
      (node (ref "JTAG") (pin "1") (pinfunction "1_1") (pintype "bidirectional"))
      (node (ref "L1") (pin "P$1") (pinfunction "1_P$1") (pintype "passive"))
      (node (ref "LT_I2C2") (pin "2") (pinfunction "VREF1_2") (pintype "bidirectional"))
      (node (ref "R10") (pin "P$2") (pinfunction "2_P$2") (pintype "passive"))
      (node (ref "R12") (pin "P$2") (pinfunction "2_P$2") (pintype "passive"))
      (node (ref "R29") (pin "P$1") (pinfunction "1_P$1") (pintype "passive"))
      (node (ref "R32") (pin "P$2") (pinfunction "2_P$2") (pintype "passive"))
      (node (ref "R33") (pin "P$2") (pinfunction "2_P$2") (pintype "passive"))
      (node (ref "R34") (pin "P$2") (pinfunction "2_P$2") (pintype "passive"))
      (node (ref "R35") (pin "P$2") (pinfunction "2_P$2") (pintype "passive"))
      (node (ref "R36") (pin "P$2") (pinfunction "2_P$2") (pintype "passive"))
      (node (ref "R37") (pin "P$2") (pinfunction "2_P$2") (pintype "passive"))
      (node (ref "R38") (pin "P$2") (pinfunction "2_P$2") (pintype "passive"))
      (node (ref "R4") (pin "P$1") (pinfunction "1_P$1") (pintype "passive"))
      (node (ref "R5") (pin "P$1") (pinfunction "1_P$1") (pintype "passive"))
      (node (ref "R7") (pin "P$2") (pinfunction "2_P$2") (pintype "passive"))
      (node (ref "R8") (pin "P$2") (pinfunction "2_P$2") (pintype "passive"))
      (node (ref "U2") (pin "1") (pinfunction "VBAT_1") (pintype "power_in"))
      (node (ref "U2") (pin "19") (pinfunction "VDD4_19") (pintype "bidirectional"))
      (node (ref "U2") (pin "32") (pinfunction "VDD1_32") (pintype "power_in"))
      (node (ref "U2") (pin "48") (pinfunction "VDD2_48") (pintype "power_in"))
      (node (ref "U2") (pin "64") (pinfunction "VDD3_64") (pintype "power_in"))
      (node (ref "VREG1") (pin "3") (pinfunction "VOUT_3") (pintype "bidirectional"))
    )
    (net (code "2") (name "+5V") (class "Default")
      (node (ref "C1") (pin "P$1") (pinfunction "1_P$1") (pintype "passive"))
      (node (ref "C2") (pin "P$1") (pinfunction "1_P$1") (pintype "passive"))
      (node (ref "C26") (pin "P$1") (pinfunction "1_P$1") (pintype "passive"))
      (node (ref "CON_ANALOG1") (pin "3") (pinfunction "3_3") (pintype "bidirectional"))
      (node (ref "CON_ANALOG2") (pin "3") (pinfunction "3_3") (pintype "bidirectional"))
      (node (ref "IC9") (pin "5") (pinfunction "VOUT_5") (pintype "bidirectional"))
      (node (ref "JP3") (pin "P$2") (pinfunction "2_P$2") (pintype "passive"))
      (node (ref "R25") (pin "P$2") (pinfunction "2_P$2") (pintype "passive"))
      (node (ref "R43") (pin "P$2") (pinfunction "2_P$2") (pintype "passive"))
      (node (ref "R44") (pin "P$2") (pinfunction "2_P$2") (pintype "passive"))
      (node (ref "R56") (pin "P$2") (pinfunction "2_P$2") (pintype "passive"))
      (node (ref "R60") (pin "P$1") (pinfunction "1_P$1") (pintype "passive"))
      (node (ref "U1") (pin "3") (pinfunction "VDD_3") (pintype "power_in"))
    )
    (net (code "3") (name "ADC_1") (class "Default")
      (node (ref "CON_ANALOG1") (pin "4") (pinfunction "4_4") (pintype "bidirectional"))
      (node (ref "LED6") (pin "C") (pinfunction "C_C") (pintype "passive"))
      (node (ref "U2") (pin "11") (pinfunction "PC3-ADC13/ETH_MII_TX_CLK_11") (pintype "bidirectional"))
    )
    (net (code "4") (name "ADC_2") (class "Default")
      (node (ref "CON_ANALOG1") (pin "5") (pinfunction "5_5") (pintype "bidirectional"))
      (node (ref "LED7") (pin "C") (pinfunction "C_C") (pintype "passive"))
      (node (ref "U2") (pin "8") (pinfunction "PC0-ADC10_8") (pintype "bidirectional"))
    )
    (net (code "5") (name "ADC_3") (class "Default")
      (node (ref "CON_ANALOG1") (pin "6") (pinfunction "6_6") (pintype "bidirectional"))
      (node (ref "LED8") (pin "C") (pinfunction "C_C") (pintype "passive"))
      (node (ref "U2") (pin "9") (pinfunction "PC1-ADC11/ETH_(R)MII_MDC_9") (pintype "bidirectional"))
    )
    (net (code "6") (name "ADC_4") (class "Default")
      (node (ref "CON_ANALOG2") (pin "4") (pinfunction "4_4") (pintype "bidirectional"))
      (node (ref "LED4") (pin "C") (pinfunction "C_C") (pintype "passive"))
      (node (ref "U2") (pin "25") (pinfunction "PC5-ADC15ETH_(R)MII_RXD1_25") (pintype "bidirectional"))
    )
    (net (code "7") (name "ADC_6") (class "Default")
      (node (ref "CON_ANALOG2") (pin "5") (pinfunction "5_5") (pintype "bidirectional"))
      (node (ref "LED3") (pin "C") (pinfunction "C_C") (pintype "passive"))
      (node (ref "U2") (pin "10") (pinfunction "PC2-ADC12/ETH_MII_TXD2_10") (pintype "bidirectional"))
    )
    (net (code "8") (name "BARO_DRDY") (class "Default")
      (node (ref "U2") (pin "26") (pinfunction "PB0-ADC8/TIM3CH3/ETH_MII_RXD2-TIM1CH2N_26") (pintype "bidirectional"))
    )
    (net (code "9") (name "BOOT0") (class "Default")
      (node (ref "CON_ANALOG2") (pin "6") (pinfunction "6_6") (pintype "bidirectional"))
      (node (ref "R1") (pin "P$2") (pinfunction "2_P$2") (pintype "passive"))
      (node (ref "R2") (pin "P$1") (pinfunction "1_P$1") (pintype "passive"))
      (node (ref "R30") (pin "P$2") (pinfunction "2_P$2") (pintype "passive"))
      (node (ref "U2") (pin "60") (pinfunction "BOOT0_60") (pintype "input"))
    )
    (net (code "10") (name "BOOT1") (class "Default")
      (node (ref "U2") (pin "28") (pinfunction "PB2/BOOT1_28") (pintype "bidirectional"))
    )
    (net (code "11") (name "CAN_H") (class "Default")
      (node (ref "JP21") (pin "5") (pinfunction "5_5") (pintype "passive"))
      (node (ref "R58") (pin "P$1") (pinfunction "1_P$1") (pintype "passive"))
      (node (ref "U1") (pin "7") (pinfunction "CANH_7") (pintype "bidirectional"))
    )
    (net (code "12") (name "CAN_L") (class "Default")
      (node (ref "JP21") (pin "4") (pinfunction "4_4") (pintype "passive"))
      (node (ref "R59") (pin "P$2") (pinfunction "2_P$2") (pintype "passive"))
      (node (ref "U1") (pin "6") (pinfunction "CANL_6") (pintype "bidirectional"))
    )
    (net (code "13") (name "CAN_RX") (class "Default")
      (node (ref "U1") (pin "4") (pinfunction "RXD_4") (pintype "output"))
      (node (ref "U2") (pin "61") (pinfunction "PB8-TIM4CH3/ETH_MII_TXD3-I2C1SCL/CAN1RX_61") (pintype "bidirectional"))
    )
    (net (code "14") (name "CAN_TX") (class "Default")
      (node (ref "U1") (pin "1") (pinfunction "TXD_1") (pintype "input"))
      (node (ref "U2") (pin "62") (pinfunction "PB9-TIM4CH4-I2C1SDA/CAN1TX_62") (pintype "bidirectional"))
    )
    (net (code "15") (name "EXTSPI_DRDY") (class "Default")
      (node (ref "JP22") (pin "7") (pinfunction "7_7") (pintype "passive"))
      (node (ref "U2") (pin "27") (pinfunction "PB1-ADC9/TIM3CH4/ETH_MII_RXD3-TIM1CH3N_27") (pintype "bidirectional"))
    )
    (net (code "16") (name "EXTSPI_MISO") (class "Default")
      (node (ref "JP22") (pin "4") (pinfunction "4_4") (pintype "passive"))
      (node (ref "U2") (pin "22") (pinfunction "PA6-SPI1MISO/ADC6/TIM3CH1-TIM1BKIN_22") (pintype "bidirectional"))
    )
    (net (code "17") (name "EXTSPI_MOSI") (class "Default")
      (node (ref "JP22") (pin "3") (pinfunction "3_3") (pintype "passive"))
      (node (ref "U2") (pin "23") (pinfunction "PA7-SPI1MOSI/ADC7/TIM3CH2/ETH_MII_RX_DV/ETH_RMII_CRS_DV-TIM1CH1N_23") (pintype "bidirectional"))
    )
    (net (code "18") (name "EXTSPI_SCK") (class "Default")
      (node (ref "JP22") (pin "5") (pinfunction "5_5") (pintype "passive"))
      (node (ref "U2") (pin "21") (pinfunction "PA5-SPI1SCK/DAC2/ADC5_21") (pintype "bidirectional"))
    )
    (net (code "19") (name "EXTSPI_SS") (class "Default")
      (node (ref "JP22") (pin "6") (pinfunction "6_6") (pintype "passive"))
      (node (ref "U2") (pin "20") (pinfunction "PA4-SPI1NSS/DAC1/USART2CK/ADC4-SPI3NSS/I2S3WS_20") (pintype "bidirectional"))
    )
    (net (code "20") (name "GND") (class "Default")
      (node (ref "C1") (pin "P$2") (pinfunction "2_P$2") (pintype "passive"))
      (node (ref "C10") (pin "P$1") (pinfunction "1_P$1") (pintype "passive"))
      (node (ref "C11") (pin "P$1") (pinfunction "1_P$1") (pintype "passive"))
      (node (ref "C12") (pin "P$1") (pinfunction "1_P$1") (pintype "passive"))
      (node (ref "C13") (pin "P$2") (pinfunction "2_P$2") (pintype "passive"))
      (node (ref "C14") (pin "P$1") (pinfunction "1_P$1") (pintype "passive"))
      (node (ref "C15") (pin "P$2") (pinfunction "2_P$2") (pintype "passive"))
      (node (ref "C2") (pin "P$2") (pinfunction "2_P$2") (pintype "passive"))
      (node (ref "C26") (pin "P$2") (pinfunction "2_P$2") (pintype "passive"))
      (node (ref "C27") (pin "P$1") (pinfunction "1_P$1") (pintype "passive"))
      (node (ref "C28") (pin "-") (pinfunction "-_-") (pintype "passive"))
      (node (ref "C3") (pin "P$2") (pinfunction "2_P$2") (pintype "passive"))
      (node (ref "C31") (pin "P$1") (pinfunction "1_P$1") (pintype "passive"))
      (node (ref "C35") (pin "P$2") (pinfunction "2_P$2") (pintype "passive"))
      (node (ref "C36") (pin "P$2") (pinfunction "2_P$2") (pintype "passive"))
      (node (ref "C37") (pin "-") (pinfunction "-_-") (pintype "passive"))
      (node (ref "C38") (pin "P$2") (pinfunction "2_P$2") (pintype "passive"))
      (node (ref "C39") (pin "-") (pinfunction "-_-") (pintype "passive"))
      (node (ref "C4") (pin "P$1") (pinfunction "1_P$1") (pintype "passive"))
      (node (ref "C42") (pin "P$1") (pinfunction "1_P$1") (pintype "passive"))
      (node (ref "C5") (pin "P$1") (pinfunction "1_P$1") (pintype "passive"))
      (node (ref "C6") (pin "P$2") (pinfunction "2_P$2") (pintype "passive"))
      (node (ref "C7") (pin "P$1") (pinfunction "1_P$1") (pintype "passive"))
      (node (ref "C9") (pin "P$2") (pinfunction "2_P$2") (pintype "passive"))
      (node (ref "CON_ANALOG1") (pin "1") (pinfunction "1_1") (pintype "bidirectional"))
      (node (ref "CON_ANALOG2") (pin "1") (pinfunction "1_1") (pintype "bidirectional"))
      (node (ref "CON_USB_MICRO") (pin "GND_LEFT") (pinfunction "S1_GND_LEFT") (pintype "passive"))
      (node (ref "CON_USB_MICRO") (pin "GND_RIGHT") (pinfunction "S2_GND_RIGHT") (pintype "passive"))
      (node (ref "CON_USB_MICRO") (pin "GND_UP_LEFT") (pinfunction "S3_GND_UP_LEFT") (pintype "passive"))
      (node (ref "CON_USB_MICRO") (pin "GND_UP_RIGHT") (pinfunction "S4_GND_UP_RIGHT") (pintype "passive"))
      (node (ref "CON_USB_MICRO") (pin "PIN_5") (pinfunction "5_PIN_5") (pintype "input"))
      (node (ref "IC9") (pin "2") (pinfunction "GND_2") (pintype "bidirectional"))
      (node (ref "IMU") (pin "P$1") (pinfunction "GND1_P$1") (pintype "bidirectional"))
      (node (ref "IMU") (pin "P$13") (pinfunction "ACC_DRDY_P$13") (pintype "bidirectional"))
      (node (ref "IMU") (pin "P$14") (pinfunction "GND4_P$14") (pintype "bidirectional"))
      (node (ref "IMU") (pin "P$7") (pinfunction "GND2_P$7") (pintype "bidirectional"))
      (node (ref "J1") (pin "1") (pinfunction "1_1") (pintype "bidirectional"))
      (node (ref "J2") (pin "1") (pinfunction "1_1") (pintype "bidirectional"))
      (node (ref "J3") (pin "1") (pinfunction "1_1") (pintype "bidirectional"))
      (node (ref "J4") (pin "1") (pinfunction "1_1") (pintype "bidirectional"))
      (node (ref "J5") (pin "1") (pinfunction "1_1") (pintype "bidirectional"))
      (node (ref "J6") (pin "1") (pinfunction "1_1") (pintype "bidirectional"))
      (node (ref "J7") (pin "1") (pinfunction "1_1") (pintype "bidirectional"))
      (node (ref "J8") (pin "1") (pinfunction "1_1") (pintype "bidirectional"))
      (node (ref "JP12") (pin "P$2") (pinfunction "2_P$2") (pintype "passive"))
      (node (ref "JP13") (pin "P$2") (pinfunction "2_P$2") (pintype "passive"))
      (node (ref "JP14") (pin "1") (pinfunction "1_1") (pintype "passive"))
      (node (ref "JP15") (pin "1") (pinfunction "1_1") (pintype "passive"))
      (node (ref "JP16") (pin "1") (pinfunction "1_1") (pintype "passive"))
      (node (ref "JP17") (pin "1") (pinfunction "1_1") (pintype "passive"))
      (node (ref "JP20") (pin "1") (pinfunction "1_1") (pintype "passive"))
      (node (ref "JP20") (pin "4") (pinfunction "4_4") (pintype "passive"))
      (node (ref "JP21") (pin "1") (pinfunction "1_1") (pintype "passive"))
      (node (ref "JP22") (pin "1") (pinfunction "1_1") (pintype "passive"))
      (node (ref "JTAG") (pin "3") (pinfunction "3_3") (pintype "bidirectional"))
      (node (ref "JTAG") (pin "5") (pinfunction "5_5") (pintype "bidirectional"))
      (node (ref "JTAG") (pin "7") (pinfunction "7_7") (pintype "bidirectional"))
      (node (ref "JTAG") (pin "9") (pinfunction "9_9") (pintype "bidirectional"))
      (node (ref "LEDVIN") (pin "C") (pinfunction "C_C") (pintype "passive"))
      (node (ref "LT_I2C2") (pin "1") (pinfunction "GND_1") (pintype "bidirectional"))
      (node (ref "Q1") (pin "P$2") (pinfunction "P$2_P$2") (pintype "bidirectional"))
      (node (ref "Q1") (pin "P$4") (pinfunction "P$4_P$4") (pintype "bidirectional"))
      (node (ref "R18") (pin "P$2") (pinfunction "2_P$2") (pintype "passive"))
      (node (ref "R2") (pin "P$2") (pinfunction "2_P$2") (pintype "passive"))
      (node (ref "R30") (pin "P$1") (pinfunction "1_P$1") (pintype "passive"))
      (node (ref "R55") (pin "P$1") (pinfunction "1_P$1") (pintype "passive"))
      (node (ref "R61") (pin "P$2") (pinfunction "2_P$2") (pintype "passive"))
      (node (ref "U1") (pin "2") (pinfunction "VSS_2") (pintype "power_in"))
      (node (ref "U2") (pin "12") (pinfunction "VSSA_12") (pintype "power_in"))
      (node (ref "U2") (pin "18") (pinfunction "VSS4_18") (pintype "bidirectional"))
      (node (ref "U2") (pin "63") (pinfunction "VSS3_63") (pintype "power_in"))
      (node (ref "VREG1") (pin "5") (pinfunction "GND4_5") (pintype "bidirectional"))
      (node (ref "VREG1") (pin "6") (pinfunction "GND3_6") (pintype "bidirectional"))
      (node (ref "VREG1") (pin "7") (pinfunction "GND2_7") (pintype "bidirectional"))
      (node (ref "VREG1") (pin "8") (pinfunction "GND1_8") (pintype "bidirectional"))
    )
    (net (code "21") (name "I2C2_SCL") (class "Default")
      (node (ref "IMU") (pin "P$10") (pinfunction "SCL_P$10") (pintype "bidirectional"))
      (node (ref "JP14") (pin "3") (pinfunction "3_3") (pintype "passive"))
      (node (ref "R4") (pin "P$2") (pinfunction "2_P$2") (pintype "passive"))
      (node (ref "U2") (pin "29") (pinfunction "PB10-I2C2SCL/USART3TX/ETH_MII_RX_ER-TIM2CH3_29") (pintype "bidirectional"))
    )
    (net (code "22") (name "I2C2_SDA") (class "Default")
      (node (ref "IMU") (pin "P$11") (pinfunction "SDA_P$11") (pintype "bidirectional"))
      (node (ref "JP14") (pin "4") (pinfunction "4_4") (pintype "passive"))
      (node (ref "R5") (pin "P$2") (pinfunction "2_P$2") (pintype "passive"))
      (node (ref "U2") (pin "30") (pinfunction "PB11-I2C2SDA/USART3RX/ETH_(R)MII_TX_EN-TIM2CH4_30") (pintype "bidirectional"))
    )
    (net (code "23") (name "IMU_ACC_CS") (class "Default")
      (node (ref "IMU") (pin "P$12") (pinfunction "ACC_CS_P$12") (pintype "bidirectional"))
      (node (ref "U2") (pin "33") (pinfunction "PB12-SPI2NSS/I2S2WS/I2C2SMBA/USART3CK/TIM1BKIN/CAN2RX/ETH_(R)MII_TXD0_33") (pintype "bidirectional"))
    )
    (net (code "24") (name "IMU_GYRO_DRDY") (class "Default")
      (node (ref "IMU") (pin "P$9") (pinfunction "GYRO_DRDY_P$9") (pintype "bidirectional"))
      (node (ref "U2") (pin "3") (pinfunction "PC14-OSC32_IN_3") (pintype "bidirectional"))
    )
    (net (code "25") (name "IMU_GYRO_SS") (class "Default")
      (node (ref "IMU") (pin "P$8") (pinfunction "GND3_P$8") (pintype "bidirectional"))
      (node (ref "U2") (pin "2") (pinfunction "PC13-TAMPER-RTC_2") (pintype "bidirectional"))
    )
    (net (code "26") (name "IMU_MAG_DRDY") (class "Default")
      (node (ref "IMU") (pin "P$6") (pinfunction "MAG_DRDY_P$6") (pintype "bidirectional"))
      (node (ref "R29") (pin "P$2") (pinfunction "2_P$2") (pintype "passive"))
      (node (ref "U2") (pin "57") (pinfunction "PB5-I2C1SMBA/SPI3MOSI/ETH_(R)MII_PPS_OUT/I2S3SD-TIM3CH2/SPI1MOSI/CAN2RX_57") (pintype "bidirectional"))
    )
    (net (code "27") (name "IMU_SPI_MISO") (class "Default")
      (node (ref "IMU") (pin "P$3") (pinfunction "MISO_P$3") (pintype "bidirectional"))
      (node (ref "U2") (pin "35") (pinfunction "PB14-SPI2MISO/USART3RTS/TIM1CH2N_35") (pintype "bidirectional"))
    )
    (net (code "28") (name "IMU_SPI_MOSI") (class "Default")
      (node (ref "IMU") (pin "P$4") (pinfunction "MOSI_P$4") (pintype "bidirectional"))
      (node (ref "U2") (pin "36") (pinfunction "PB15-SPI2MOSI/I2S2SD/TIM1CH3N_36") (pintype "bidirectional"))
    )
    (net (code "29") (name "IMU_SPI_SCK") (class "Default")
      (node (ref "IMU") (pin "P$5") (pinfunction "SCK_P$5") (pintype "bidirectional"))
      (node (ref "U2") (pin "34") (pinfunction "PB13-SPI2SCK/I2S2CK/USART3CTS/TIM1CH1N/CAN2TX/ETH_(R)MII_TXD1_34") (pintype "bidirectional"))
    )
    (net (code "30") (name "JTAG_RST") (class "Default")
      (node (ref "C27") (pin "P$2") (pinfunction "2_P$2") (pintype "passive"))
      (node (ref "JTAG") (pin "10") (pinfunction "10_10") (pintype "bidirectional"))
      (node (ref "R7") (pin "P$1") (pinfunction "1_P$1") (pintype "passive"))
      (node (ref "U2") (pin "7") (pinfunction "NRST_7") (pintype "bidirectional"))
    )
    (net (code "31") (name "JTAG_TCK") (class "Default")
      (node (ref "JTAG") (pin "4") (pinfunction "4_4") (pintype "bidirectional"))
      (node (ref "U2") (pin "49") (pinfunction "PA14/JTCK/SWCLK_49") (pintype "bidirectional"))
    )
    (net (code "32") (name "JTAG_TDI") (class "Default")
      (node (ref "JTAG") (pin "8") (pinfunction "8_8") (pintype "bidirectional"))
      (node (ref "U2") (pin "50") (pinfunction "PA15/JTDI-SPI3NSS/I2S3WS-TIM2CH1ETR/SPI1NSS_50") (pintype "bidirectional"))
    )
    (net (code "33") (name "JTAG_TDO") (class "Default")
      (node (ref "JTAG") (pin "6") (pinfunction "6_6") (pintype "bidirectional"))
      (node (ref "U2") (pin "55") (pinfunction "PB3/JTDO-SPI3SCK/I2S3CK-TIM2CH2/TRACESWO/SPI1SCK_55") (pintype "bidirectional"))
    )
    (net (code "34") (name "JTAG_TMS") (class "Default")
      (node (ref "JTAG") (pin "2") (pinfunction "2_2") (pintype "bidirectional"))
      (node (ref "U2") (pin "46") (pinfunction "PA13/JTMS/SWDIO_46") (pintype "bidirectional"))
    )
    (net (code "35") (name "JTAG_TRST") (class "Default")
      (node (ref "JP15") (pin "4") (pinfunction "4_4") (pintype "passive"))
      (node (ref "LED2") (pin "C") (pinfunction "C_C") (pintype "passive"))
      (node (ref "U2") (pin "56") (pinfunction "PB4/JNTRST-SPI3MISO-TIM3CH1/SPI1MISO_56") (pintype "bidirectional"))
    )
    (net (code "36") (name "LED1") (class "Default")
      (node (ref "LED1") (pin "C") (pinfunction "C_C") (pintype "passive"))
      (node (ref "U2") (pin "41") (pinfunction "PA8-USART1CK/OTG_FS_SOF/MCO/TIM1CH1_41") (pintype "bidirectional"))
    )
    (net (code "37") (name "LED2") (class "Default")
      (node (ref "LED5") (pin "C") (pinfunction "C_C") (pintype "passive"))
      (node (ref "U2") (pin "4") (pinfunction "PC15-OSC32_OUT_4") (pintype "bidirectional"))
    )
    (net (code "38") (name "LT_I2C1_SCL") (class "Default")
      (node (ref "JP10") (pin "P$2") (pinfunction "2_P$2") (pintype "passive"))
      (node (ref "JP21") (pin "6") (pinfunction "6_6") (pintype "passive"))
      (node (ref "LT_I2C2") (pin "6") (pinfunction "SCL2_6") (pintype "bidirectional"))
      (node (ref "R44") (pin "P$1") (pinfunction "1_P$1") (pintype "passive"))
    )
    (net (code "39") (name "LT_I2C1_SDA") (class "Default")
      (node (ref "JP11") (pin "P$2") (pinfunction "2_P$2") (pintype "passive"))
      (node (ref "JP21") (pin "7") (pinfunction "7_7") (pintype "passive"))
      (node (ref "LT_I2C2") (pin "5") (pinfunction "SDA2_5") (pintype "bidirectional"))
      (node (ref "R43") (pin "P$1") (pinfunction "1_P$1") (pintype "passive"))
    )
    (net (code "40") (name "Net-(C13-1)") (class "Default")
      (node (ref "C13") (pin "P$1") (pinfunction "1_P$1") (pintype "passive"))
      (node (ref "IC9") (pin "4") (pinfunction "BYPASS_4") (pintype "bidirectional"))
    )
    (net (code "41") (name "Net-(C15-1)") (class "Default")
      (node (ref "C15") (pin "P$1") (pinfunction "1_P$1") (pintype "passive"))
      (node (ref "LT_I2C2") (pin "7") (pinfunction "VREF2_7") (pintype "bidirectional"))
      (node (ref "LT_I2C2") (pin "8") (pinfunction "EN_8") (pintype "bidirectional"))
      (node (ref "R25") (pin "P$1") (pinfunction "1_P$1") (pintype "passive"))
    )
    (net (code "42") (name "Net-(C31-2)") (class "Default")
      (node (ref "C28") (pin "+") (pinfunction "+_+") (pintype "passive"))
      (node (ref "C31") (pin "P$2") (pinfunction "2_P$2") (pintype "passive"))
      (node (ref "L1") (pin "P$2") (pinfunction "2_P$2") (pintype "passive"))
      (node (ref "U2") (pin "13") (pinfunction "VDDA_13") (pintype "power_in"))
    )
    (net (code "43") (name "Net-(C35-1)") (class "Default")
      (node (ref "C35") (pin "P$1") (pinfunction "1_P$1") (pintype "passive"))
      (node (ref "VREG1") (pin "4") (pinfunction "BYP_4") (pintype "bidirectional"))
    )
    (net (code "44") (name "Net-(C42-2)") (class "Default")
      (node (ref "C42") (pin "P$2") (pinfunction "2_P$2") (pintype "passive"))
      (node (ref "R58") (pin "P$2") (pinfunction "2_P$2") (pintype "passive"))
      (node (ref "R59") (pin "P$1") (pinfunction "1_P$1") (pintype "passive"))
      (node (ref "R60") (pin "P$2") (pinfunction "2_P$2") (pintype "passive"))
      (node (ref "R61") (pin "P$1") (pinfunction "1_P$1") (pintype "passive"))
    )
    (net (code "45") (name "Net-(R8-1)") (class "Default")
      (node (ref "LED2") (pin "A") (pinfunction "A_A") (pintype "passive"))
      (node (ref "R8") (pin "P$1") (pinfunction "1_P$1") (pintype "passive"))
    )
    (net (code "46") (name "Net-(R9-1)") (class "Default")
      (node (ref "J1") (pin "2") (pinfunction "2_2") (pintype "bidirectional"))
      (node (ref "R9") (pin "P$1") (pinfunction "1_P$1") (pintype "passive"))
    )
    (net (code "47") (name "Net-(R10-1)") (class "Default")
      (node (ref "LED1") (pin "A") (pinfunction "A_A") (pintype "passive"))
      (node (ref "R10") (pin "P$1") (pinfunction "1_P$1") (pintype "passive"))
    )
    (net (code "48") (name "Net-(R11-1)") (class "Default")
      (node (ref "J2") (pin "2") (pinfunction "2_2") (pintype "bidirectional"))
      (node (ref "R11") (pin "P$1") (pinfunction "1_P$1") (pintype "passive"))
    )
    (net (code "49") (name "Net-(R12-1)") (class "Default")
      (node (ref "LED5") (pin "A") (pinfunction "A_A") (pintype "passive"))
      (node (ref "R12") (pin "P$1") (pinfunction "1_P$1") (pintype "passive"))
    )
    (net (code "50") (name "Net-(R13-1)") (class "Default")
      (node (ref "J4") (pin "2") (pinfunction "2_2") (pintype "bidirectional"))
      (node (ref "R13") (pin "P$1") (pinfunction "1_P$1") (pintype "passive"))
    )
    (net (code "51") (name "Net-(R14-1)") (class "Default")
      (node (ref "J5") (pin "2") (pinfunction "2_2") (pintype "bidirectional"))
      (node (ref "R14") (pin "P$1") (pinfunction "1_P$1") (pintype "passive"))
    )
    (net (code "52") (name "Net-(R15-1)") (class "Default")
      (node (ref "J6") (pin "2") (pinfunction "2_2") (pintype "bidirectional"))
      (node (ref "R15") (pin "P$1") (pinfunction "1_P$1") (pintype "passive"))
    )
    (net (code "53") (name "Net-(R16-1)") (class "Default")
      (node (ref "J7") (pin "2") (pinfunction "2_2") (pintype "bidirectional"))
      (node (ref "R16") (pin "P$1") (pinfunction "1_P$1") (pintype "passive"))
    )
    (net (code "54") (name "Net-(R19-1)") (class "Default")
      (node (ref "J8") (pin "2") (pinfunction "2_2") (pintype "bidirectional"))
      (node (ref "R19") (pin "P$1") (pinfunction "1_P$1") (pintype "passive"))
    )
    (net (code "55") (name "Net-(R20-1)") (class "Default")
      (node (ref "J3") (pin "2") (pinfunction "2_2") (pintype "bidirectional"))
      (node (ref "R20") (pin "P$1") (pinfunction "1_P$1") (pintype "passive"))
    )
    (net (code "56") (name "Net-(R23-1)") (class "Default")
      (node (ref "LEDVIN") (pin "A") (pinfunction "A_A") (pintype "passive"))
      (node (ref "R23") (pin "P$1") (pinfunction "1_P$1") (pintype "passive"))
    )
    (net (code "57") (name "Net-(R32-1)") (class "Default")
      (node (ref "LED6") (pin "A") (pinfunction "A_A") (pintype "passive"))
      (node (ref "R32") (pin "P$1") (pinfunction "1_P$1") (pintype "passive"))
    )
    (net (code "58") (name "Net-(R35-1)") (class "Default")
      (node (ref "LED7") (pin "A") (pinfunction "A_A") (pintype "passive"))
      (node (ref "R35") (pin "P$1") (pinfunction "1_P$1") (pintype "passive"))
    )
    (net (code "59") (name "Net-(R36-1)") (class "Default")
      (node (ref "LED8") (pin "A") (pinfunction "A_A") (pintype "passive"))
      (node (ref "R36") (pin "P$1") (pinfunction "1_P$1") (pintype "passive"))
    )
    (net (code "60") (name "Net-(R37-1)") (class "Default")
      (node (ref "LED4") (pin "A") (pinfunction "A_A") (pintype "passive"))
      (node (ref "R37") (pin "P$1") (pinfunction "1_P$1") (pintype "passive"))
    )
    (net (code "61") (name "Net-(R38-1)") (class "Default")
      (node (ref "LED3") (pin "A") (pinfunction "A_A") (pintype "passive"))
      (node (ref "R38") (pin "P$1") (pinfunction "1_P$1") (pintype "passive"))
    )
    (net (code "62") (name "Net-(R55-2)") (class "Default")
      (node (ref "R55") (pin "P$2") (pinfunction "2_P$2") (pintype "passive"))
      (node (ref "R56") (pin "P$1") (pinfunction "1_P$1") (pintype "passive"))
      (node (ref "U1") (pin "8") (pinfunction "RS_8") (pintype "input"))
    )
    (net (code "63") (name "OSC_IN") (class "Default")
      (node (ref "C4") (pin "P$2") (pinfunction "2_P$2") (pintype "passive"))
      (node (ref "Q1") (pin "P$3") (pinfunction "P$3_P$3") (pintype "bidirectional"))
      (node (ref "U2") (pin "5") (pinfunction "PD0-OSC_IN-CAN1RX_5") (pintype "input"))
    )
    (net (code "64") (name "OSC_OUT") (class "Default")
      (node (ref "C6") (pin "P$1") (pinfunction "1_P$1") (pintype "passive"))
      (node (ref "Q1") (pin "P$1") (pinfunction "P$1_P$1") (pintype "bidirectional"))
      (node (ref "U2") (pin "6") (pinfunction "PD1-OSC_OUT-CAN1TX_6") (pintype "output"))
    )
    (net (code "65") (name "PC12") (class "Default")
      (node (ref "JP15") (pin "3") (pinfunction "3_3") (pintype "passive"))
      (node (ref "U2") (pin "53") (pinfunction "PC12-USART5TX-USART3CK/SPI3MOSI/I2S3SD_53") (pintype "bidirectional"))
    )
    (net (code "66") (name "S1") (class "Default")
      (node (ref "J1") (pin "3") (pinfunction "3_3") (pintype "bidirectional"))
      (node (ref "R41") (pin "P$1") (pinfunction "1_P$1") (pintype "passive"))
    )
    (net (code "67") (name "S2") (class "Default")
      (node (ref "J2") (pin "3") (pinfunction "3_3") (pintype "bidirectional"))
      (node (ref "R42") (pin "P$1") (pinfunction "1_P$1") (pintype "passive"))
    )
    (net (code "68") (name "S3") (class "Default")
      (node (ref "J3") (pin "3") (pinfunction "3_3") (pintype "bidirectional"))
      (node (ref "R45") (pin "P$1") (pinfunction "1_P$1") (pintype "passive"))
    )
    (net (code "69") (name "S4") (class "Default")
      (node (ref "J4") (pin "3") (pinfunction "3_3") (pintype "bidirectional"))
      (node (ref "R27") (pin "P$1") (pinfunction "1_P$1") (pintype "passive"))
    )
    (net (code "70") (name "S5") (class "Default")
      (node (ref "J5") (pin "3") (pinfunction "3_3") (pintype "bidirectional"))
      (node (ref "R28") (pin "P$1") (pinfunction "1_P$1") (pintype "passive"))
    )
    (net (code "71") (name "S6") (class "Default")
      (node (ref "J6") (pin "3") (pinfunction "3_3") (pintype "bidirectional"))
      (node (ref "R31") (pin "P$1") (pinfunction "1_P$1") (pintype "passive"))
    )
    (net (code "72") (name "S7") (class "Default")
      (node (ref "J7") (pin "3") (pinfunction "3_3") (pintype "bidirectional"))
      (node (ref "R39") (pin "P$1") (pinfunction "1_P$1") (pintype "passive"))
    )
    (net (code "73") (name "S8") (class "Default")
      (node (ref "J8") (pin "3") (pinfunction "3_3") (pintype "bidirectional"))
      (node (ref "R40") (pin "P$1") (pinfunction "1_P$1") (pintype "passive"))
    )
    (net (code "74") (name "SERVO_1") (class "Default")
      (node (ref "R41") (pin "P$2") (pinfunction "2_P$2") (pintype "passive"))
      (node (ref "U2") (pin "37") (pinfunction "PC6-I2S2MCK-TIM3CH1_37") (pintype "bidirectional"))
    )
    (net (code "75") (name "SERVO_2") (class "Default")
      (node (ref "R42") (pin "P$2") (pinfunction "2_P$2") (pintype "passive"))
      (node (ref "U2") (pin "38") (pinfunction "PC7-I2S3MCK-TIM3CH2_38") (pintype "bidirectional"))
    )
    (net (code "76") (name "SERVO_3") (class "Default")
      (node (ref "R45") (pin "P$2") (pinfunction "2_P$2") (pintype "passive"))
      (node (ref "U2") (pin "39") (pinfunction "PC8-TIM3CH3_39") (pintype "bidirectional"))
    )
    (net (code "77") (name "SERVO_4") (class "Default")
      (node (ref "R27") (pin "P$2") (pinfunction "2_P$2") (pintype "passive"))
      (node (ref "U2") (pin "40") (pinfunction "PC9-TIM3CH4_40") (pintype "bidirectional"))
    )
    (net (code "78") (name "SERVO_5") (class "Default")
      (node (ref "R28") (pin "P$2") (pinfunction "2_P$2") (pintype "passive"))
      (node (ref "U2") (pin "14") (pinfunction "PA0-WKUP/USART2CTS/ADC0/TIM2CH1ETR/TIM5CH1/ETH_MII_CRS_WKUP_14") (pintype "bidirectional"))
    )
    (net (code "79") (name "SERVO_6") (class "Default")
      (node (ref "R31") (pin "P$2") (pinfunction "2_P$2") (pintype "passive"))
      (node (ref "U2") (pin "15") (pinfunction "PA1-USART2RTS/ADC1/TIM5CH2/TIM2CH2/ETH_MII_RX_CLK/ETH_RMII_REF_CLK_15") (pintype "bidirectional"))
    )
    (net (code "80") (name "SERVO_7{slash}I2C1_SCL") (class "Default")
      (node (ref "JP10") (pin "P$1") (pinfunction "1_P$1") (pintype "passive"))
      (node (ref "LT_I2C2") (pin "3") (pinfunction "SCL1_3") (pintype "bidirectional"))
      (node (ref "R33") (pin "P$1") (pinfunction "1_P$1") (pintype "passive"))
      (node (ref "R39") (pin "P$2") (pinfunction "2_P$2") (pintype "passive"))
      (node (ref "U2") (pin "58") (pinfunction "PB6-I2C1SCL/TIM4CH1-USART1TX/CAN2TX_58") (pintype "bidirectional"))
    )
    (net (code "81") (name "SERVO_8{slash}I2C1_SDA") (class "Default")
      (node (ref "JP11") (pin "P$1") (pinfunction "1_P$1") (pintype "passive"))
      (node (ref "LT_I2C2") (pin "4") (pinfunction "SDA1_4") (pintype "bidirectional"))
      (node (ref "R34") (pin "P$1") (pinfunction "1_P$1") (pintype "passive"))
      (node (ref "R40") (pin "P$2") (pinfunction "2_P$2") (pintype "passive"))
      (node (ref "U2") (pin "59") (pinfunction "PB7-I2C1SDA/TIM4CH2-USART1RX_59") (pintype "bidirectional"))
    )
    (net (code "82") (name "SERVO_BUS") (class "Default")
      (node (ref "JP1") (pin "P$1") (pinfunction "1_P$1") (pintype "passive"))
      (node (ref "R11") (pin "P$2") (pinfunction "2_P$2") (pintype "passive"))
      (node (ref "R13") (pin "P$2") (pinfunction "2_P$2") (pintype "passive"))
      (node (ref "R14") (pin "P$2") (pinfunction "2_P$2") (pintype "passive"))
      (node (ref "R15") (pin "P$2") (pinfunction "2_P$2") (pintype "passive"))
      (node (ref "R16") (pin "P$2") (pinfunction "2_P$2") (pintype "passive"))
      (node (ref "R19") (pin "P$2") (pinfunction "2_P$2") (pintype "passive"))
      (node (ref "R20") (pin "P$2") (pinfunction "2_P$2") (pintype "passive"))
      (node (ref "R9") (pin "P$2") (pinfunction "2_P$2") (pintype "passive"))
    )
    (net (code "83") (name "U1_U5_POW") (class "Default")
      (node (ref "JP20") (pin "2") (pinfunction "2_2") (pintype "passive"))
      (node (ref "JP20") (pin "5") (pinfunction "5_5") (pintype "passive"))
      (node (ref "JP8") (pin "P$2") (pinfunction "2_P$2") (pintype "passive"))
      (node (ref "JP9") (pin "P$2") (pinfunction "2_P$2") (pintype "passive"))
      (node (ref "R24") (pin "P$1") (pinfunction "1_P$1") (pintype "passive"))
      (node (ref "R6") (pin "P$1") (pinfunction "1_P$1") (pintype "passive"))
    )
    (net (code "84") (name "U2_POW") (class "Default")
      (node (ref "JP16") (pin "2") (pinfunction "2_2") (pintype "passive"))
      (node (ref "JP4") (pin "P$2") (pinfunction "2_P$2") (pintype "passive"))
      (node (ref "JP5") (pin "P$2") (pinfunction "2_P$2") (pintype "passive"))
      (node (ref "R26") (pin "P$1") (pinfunction "1_P$1") (pintype "passive"))
    )
    (net (code "85") (name "U3_POW") (class "Default")
      (node (ref "JP17") (pin "2") (pinfunction "2_2") (pintype "passive"))
      (node (ref "JP6") (pin "P$2") (pinfunction "2_P$2") (pintype "passive"))
      (node (ref "JP7") (pin "P$2") (pinfunction "2_P$2") (pintype "passive"))
      (node (ref "R3") (pin "P$1") (pinfunction "1_P$1") (pintype "passive"))
    )
    (net (code "86") (name "UART1_RX") (class "Default")
      (node (ref "JP20") (pin "3") (pinfunction "3_3") (pintype "passive"))
      (node (ref "R24") (pin "P$2") (pinfunction "2_P$2") (pintype "passive"))
      (node (ref "U2") (pin "43") (pinfunction "PA10-USART1RX/TIM1CH3/OTG_FS_ID_43") (pintype "bidirectional"))
    )
    (net (code "87") (name "UART2_RX") (class "Default")
      (node (ref "JP16") (pin "4") (pinfunction "4_4") (pintype "passive"))
      (node (ref "R26") (pin "P$2") (pinfunction "2_P$2") (pintype "passive"))
      (node (ref "U2") (pin "17") (pinfunction "PA3-USART2RX/TIM5CH4/ADC3/TIM2CH4/ETH_MII_COL_17") (pintype "bidirectional"))
    )
    (net (code "88") (name "UART2_TX") (class "Default")
      (node (ref "JP16") (pin "3") (pinfunction "3_3") (pintype "passive"))
      (node (ref "U2") (pin "16") (pinfunction "PA2-USART2TX/TIM5CH3/ADC2/TIM2CH3/ETH_(R)MII_MDIO_16") (pintype "bidirectional"))
    )
    (net (code "89") (name "UART3_RX") (class "Default")
      (node (ref "JP17") (pin "4") (pinfunction "4_4") (pintype "passive"))
      (node (ref "R3") (pin "P$2") (pinfunction "2_P$2") (pintype "passive"))
      (node (ref "U2") (pin "52") (pinfunction "PC11-USART4RX-USART3RX/SPI3MISO_52") (pintype "bidirectional"))
    )
    (net (code "90") (name "UART3_TX") (class "Default")
      (node (ref "JP17") (pin "3") (pinfunction "3_3") (pintype "passive"))
      (node (ref "U2") (pin "51") (pinfunction "PC10-USART4TX-USART3TX/SPI3SCK/I2S3CK_51") (pintype "bidirectional"))
    )
    (net (code "91") (name "UART5_RX") (class "Default")
      (node (ref "JP20") (pin "6") (pinfunction "6_6") (pintype "passive"))
      (node (ref "R6") (pin "P$2") (pinfunction "2_P$2") (pintype "passive"))
      (node (ref "U2") (pin "54") (pinfunction "PD2-TIM3ETR/USART5RX_54") (pintype "bidirectional"))
    )
    (net (code "92") (name "USB_DM") (class "Default")
      (node (ref "CON_USB_MICRO") (pin "PIN_2") (pinfunction "2_PIN_2") (pintype "input"))
      (node (ref "U2") (pin "44") (pinfunction "PA11-USART1CTS/CAN1RX/OTG_FS_DM/TIM1CH4_44") (pintype "bidirectional"))
    )
    (net (code "93") (name "USB_DP") (class "Default")
      (node (ref "CON_USB_MICRO") (pin "PIN_3") (pinfunction "3_PIN_3") (pintype "input"))
      (node (ref "U2") (pin "45") (pinfunction "PA12-USART1RTS/CAN1TX/OTG_FS_DP/TIM1ETR_45") (pintype "bidirectional"))
    )
    (net (code "94") (name "USB_VBUS") (class "Default")
      (node (ref "CON_USB_MICRO") (pin "PIN_1") (pinfunction "1_PIN_1") (pintype "input"))
      (node (ref "D3") (pin "A") (pinfunction "A_A") (pintype "passive"))
      (node (ref "R1") (pin "P$1") (pinfunction "1_P$1") (pintype "passive"))
      (node (ref "U2") (pin "42") (pinfunction "PA9-USART1TX/TIM1CH2/OTG_FS_VBUS_42") (pintype "bidirectional"))
    )
    (net (code "95") (name "VREF") (class "Default")
      (node (ref "U1") (pin "5") (pinfunction "VREF_5") (pintype "power_in"))
    )
    (net (code "96") (name "VSS1") (class "Default")
      (node (ref "C7") (pin "P$2") (pinfunction "2_P$2") (pintype "passive"))
      (node (ref "JP12") (pin "P$1") (pinfunction "1_P$1") (pintype "passive"))
      (node (ref "U2") (pin "31") (pinfunction "VSS1_31") (pintype "power_in"))
    )
    (net (code "97") (name "VSS2") (class "Default")
      (node (ref "C14") (pin "P$2") (pinfunction "2_P$2") (pintype "passive"))
      (node (ref "JP13") (pin "P$1") (pinfunction "1_P$1") (pintype "passive"))
      (node (ref "U2") (pin "47") (pinfunction "VSS2_47") (pintype "power_in"))
    )
    (net (code "98") (name "V_BAT") (class "Default")
      (node (ref "JP2") (pin "P$2") (pinfunction "2_P$2") (pintype "passive"))
      (node (ref "JP21") (pin "2") (pinfunction "2_2") (pintype "passive"))
      (node (ref "R17") (pin "P$1") (pinfunction "1_P$1") (pintype "passive"))
    )
    (net (code "99") (name "V_BAT_MEAS") (class "Default")
      (node (ref "R17") (pin "P$2") (pinfunction "2_P$2") (pintype "passive"))
      (node (ref "R18") (pin "P$1") (pinfunction "1_P$1") (pintype "passive"))
      (node (ref "U2") (pin "24") (pinfunction "PC4-ADC14/ETH_(R)MII_RXD0_24") (pintype "bidirectional"))
    )
    (net (code "100") (name "V_IN") (class "Default")
      (node (ref "C3") (pin "P$1") (pinfunction "1_P$1") (pintype "passive"))
      (node (ref "C38") (pin "P$1") (pinfunction "1_P$1") (pintype "passive"))
      (node (ref "C39") (pin "+") (pinfunction "+_+") (pintype "passive"))
      (node (ref "D3") (pin "C") (pinfunction "C_C") (pintype "passive"))
      (node (ref "IC9") (pin "1") (pinfunction "VIN_1") (pintype "bidirectional"))
      (node (ref "IC9") (pin "3") (pinfunction "ON/OFF_3") (pintype "bidirectional"))
      (node (ref "IMU") (pin "P$2") (pinfunction "VCC_P$2") (pintype "bidirectional"))
      (node (ref "JP1") (pin "P$2") (pinfunction "2_P$2") (pintype "passive"))
      (node (ref "JP2") (pin "P$1") (pinfunction "1_P$1") (pintype "passive"))
      (node (ref "JP21") (pin "3") (pinfunction "3_3") (pintype "passive"))
      (node (ref "JP3") (pin "P$1") (pinfunction "1_P$1") (pintype "passive"))
      (node (ref "JP4") (pin "P$1") (pinfunction "1_P$1") (pintype "passive"))
      (node (ref "JP6") (pin "P$1") (pinfunction "1_P$1") (pintype "passive"))
      (node (ref "JP8") (pin "P$1") (pinfunction "1_P$1") (pintype "passive"))
      (node (ref "R23") (pin "P$2") (pinfunction "2_P$2") (pintype "passive"))
      (node (ref "VREG1") (pin "1") (pinfunction "ENABLE_1") (pintype "bidirectional"))
      (node (ref "VREG1") (pin "2") (pinfunction "VIN_2") (pintype "bidirectional"))
    )
    (net (code "101") (name "unconnected-(CON_USB_MICRO-4-PadPIN_4)") (class "Default")
      (node (ref "CON_USB_MICRO") (pin "PIN_4") (pinfunction "4_PIN_4") (pintype "input"))
    )
  )
)
